# SL869-GL868-Rx.net
KiCad netlist of a schematic drawn in EAGLE
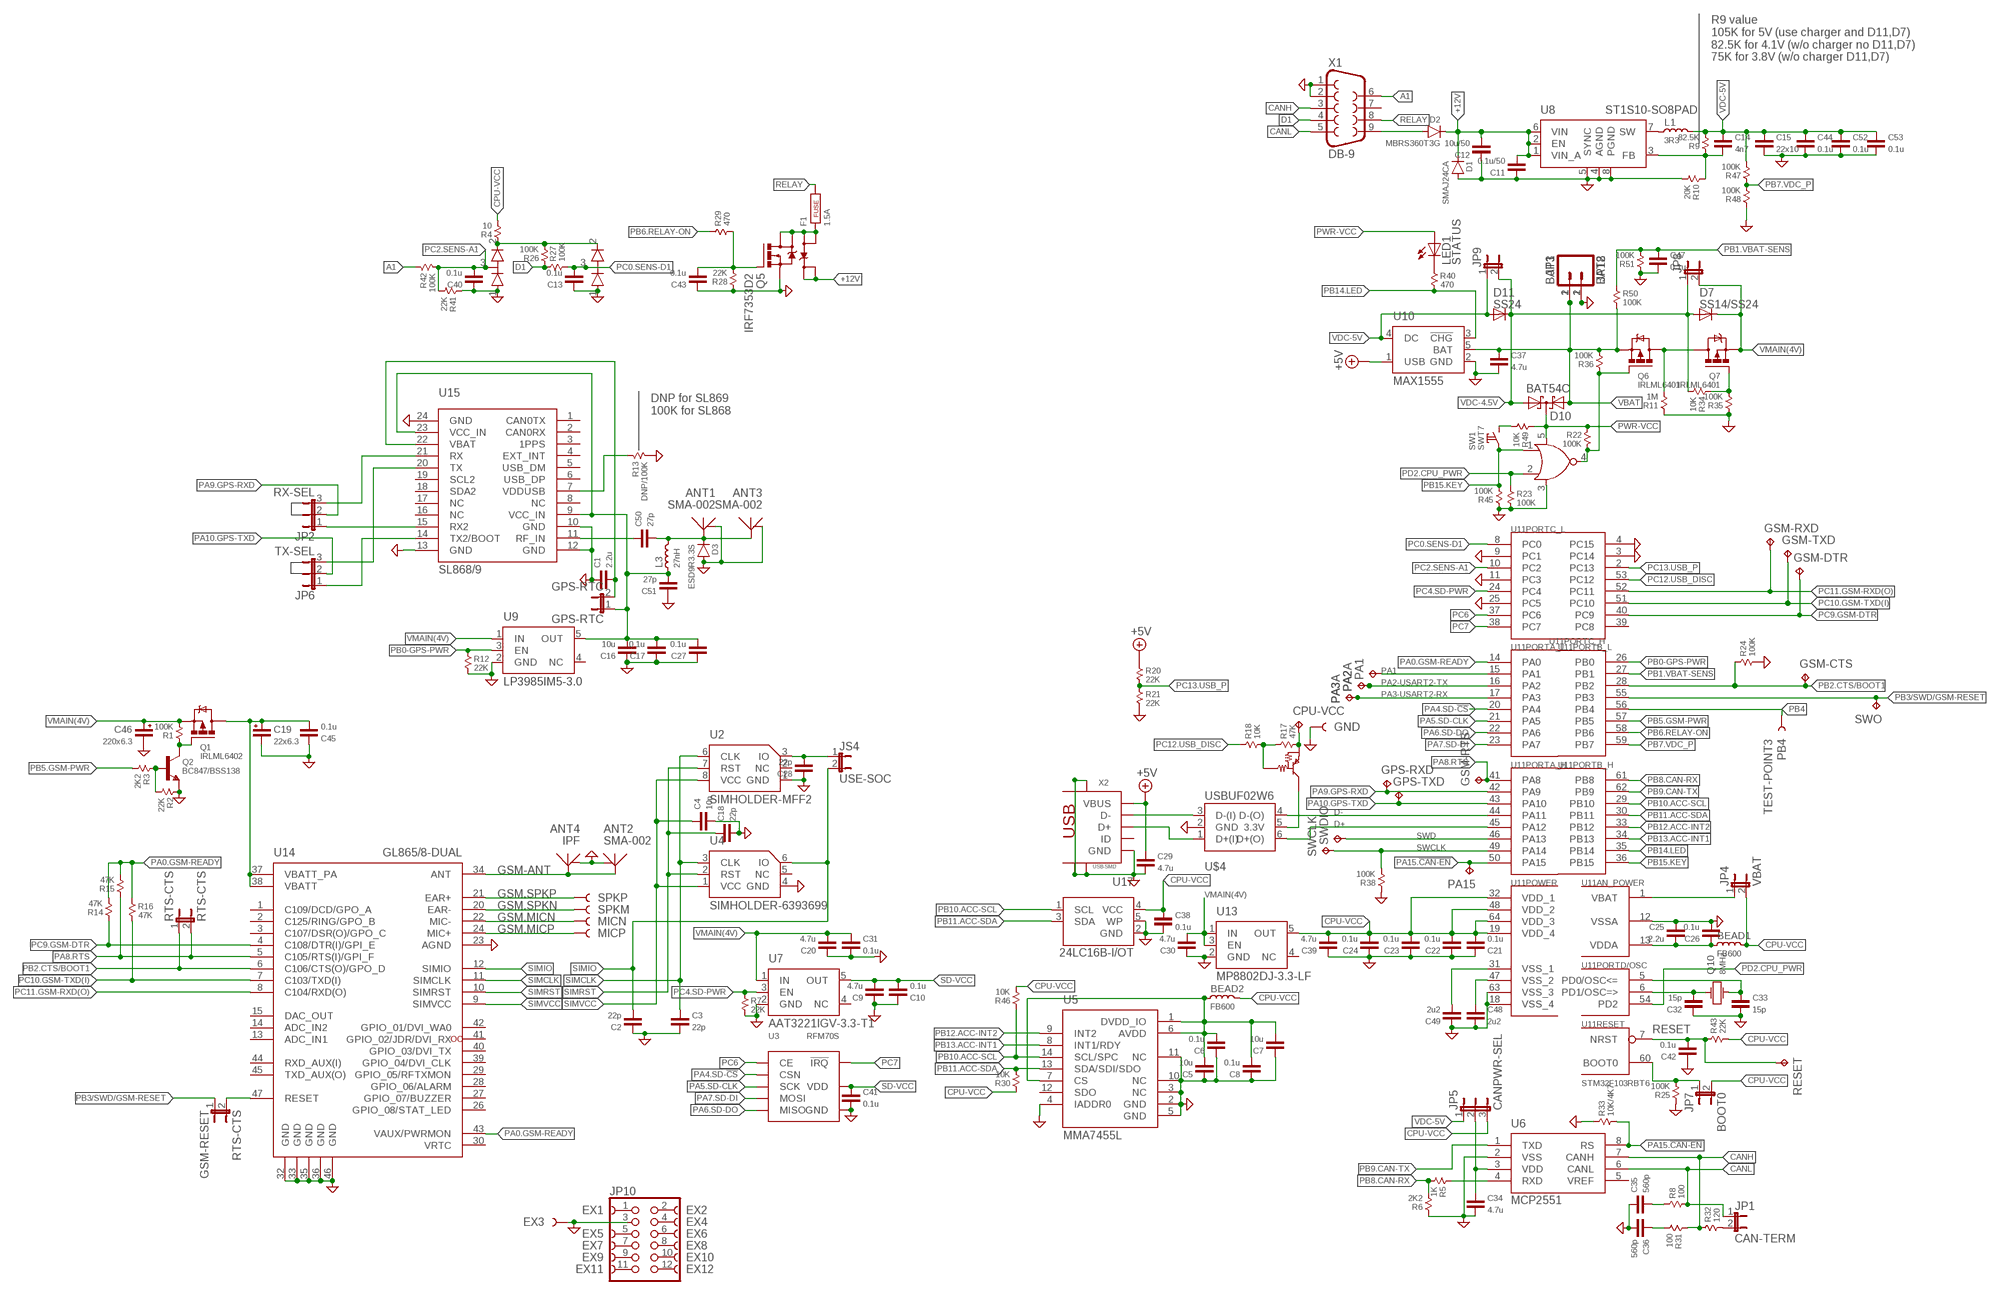
[diagram p0: schematic, sheet 1]

(export (version "E")
  (design (tool "Eeschema 10.0.6"))
  (components
    (comp (ref "ANT1")
      (value "SMA-002")
      (footprint "eagle-import:SMA-002")
      (libsource (lib "eagle-import") (part "ANTENNA-SMA-002"))
    )
    (comp (ref "ANT2")
      (value "SMA-002")
      (footprint "eagle-import:SMA-002")
      (libsource (lib "eagle-import") (part "ANTENNA-SMA-002"))
    )
    (comp (ref "ANT3")
      (value "SMA-002")
      (footprint "eagle-import:MM9329")
      (libsource (lib "eagle-import") (part "ANTENNA-IPF"))
    )
    (comp (ref "ANT4")
      (value "IPF")
      (footprint "eagle-import:MM9329")
      (libsource (lib "eagle-import") (part "ANTENNA-IPF"))
    )
    (comp (ref "BEAD1")
      (value "FB600")
      (footprint "eagle-import:0603")
      (libsource (lib "eagle-import") (part "INDUCTOR-0603"))
    )
    (comp (ref "BEAD2")
      (value "FB600")
      (footprint "eagle-import:0603")
      (libsource (lib "eagle-import") (part "INDUCTOR-0603"))
    )
    (comp (ref "C1")
      (value "2.2u")
      (footprint "eagle-import:0603")
      (libsource (lib "eagle-import") (part "CAP-0603"))
    )
    (comp (ref "C2")
      (value "22p")
      (footprint "eagle-import:0603")
      (libsource (lib "eagle-import") (part "CAP-0603"))
    )
    (comp (ref "C3")
      (value "22p")
      (footprint "eagle-import:0603")
      (libsource (lib "eagle-import") (part "CAP-0603"))
    )
    (comp (ref "C4")
      (value "10n")
      (footprint "eagle-import:0603")
      (libsource (lib "eagle-import") (part "CAP-0603"))
    )
    (comp (ref "C5")
      (value "10u")
      (footprint "eagle-import:0603")
      (libsource (lib "eagle-import") (part "CAP-0603"))
    )
    (comp (ref "C6")
      (value "0.1u")
      (footprint "eagle-import:0603")
      (libsource (lib "eagle-import") (part "CAP-0603"))
    )
    (comp (ref "C7")
      (value "10u")
      (footprint "eagle-import:0603")
      (libsource (lib "eagle-import") (part "CAP-0603"))
    )
    (comp (ref "C8")
      (value "0.1u")
      (footprint "eagle-import:0603")
      (libsource (lib "eagle-import") (part "CAP-0603"))
    )
    (comp (ref "C9")
      (value "4.7u")
      (footprint "eagle-import:0603")
      (libsource (lib "eagle-import") (part "CAP-0603"))
    )
    (comp (ref "C10")
      (value "0.1u")
      (footprint "eagle-import:0603")
      (libsource (lib "eagle-import") (part "CAP-0603"))
    )
    (comp (ref "C11")
      (value "0.1u/50")
      (footprint "eagle-import:0603")
      (libsource (lib "eagle-import") (part "CAP-0603"))
    )
    (comp (ref "C12")
      (value "10u/50")
      (footprint "eagle-import:1206")
      (libsource (lib "eagle-import") (part "CAP-1206"))
    )
    (comp (ref "C13")
      (value "0.1u")
      (footprint "eagle-import:0603")
      (libsource (lib "eagle-import") (part "CAP-0603"))
    )
    (comp (ref "C14")
      (value "4n7")
      (footprint "eagle-import:0603")
      (libsource (lib "eagle-import") (part "CAP-0603"))
    )
    (comp (ref "C15")
      (value "22x10")
      (footprint "eagle-import:1206")
      (libsource (lib "eagle-import") (part "CAP-1206"))
    )
    (comp (ref "C16")
      (value "10u")
      (footprint "eagle-import:0603")
      (libsource (lib "eagle-import") (part "CAP-0603"))
    )
    (comp (ref "C17")
      (value "0.1u")
      (footprint "eagle-import:0603")
      (libsource (lib "eagle-import") (part "CAP-0603"))
    )
    (comp (ref "C18")
      (value "22p")
      (footprint "eagle-import:0603")
      (libsource (lib "eagle-import") (part "CAP-0603"))
    )
    (comp (ref "C19")
      (value "22x6.3")
      (footprint "eagle-import:CT3528")
      (libsource (lib "eagle-import") (part "CAP-POL-3528"))
    )
    (comp (ref "C20")
      (value "4.7u")
      (footprint "eagle-import:0603")
      (libsource (lib "eagle-import") (part "CAP-0603"))
    )
    (comp (ref "C21")
      (value "0.1u")
      (footprint "eagle-import:0603")
      (libsource (lib "eagle-import") (part "CAP-0603"))
    )
    (comp (ref "C22")
      (value "0.1u")
      (footprint "eagle-import:0603")
      (libsource (lib "eagle-import") (part "CAP-0603"))
    )
    (comp (ref "C23")
      (value "0.1u")
      (footprint "eagle-import:0603")
      (libsource (lib "eagle-import") (part "CAP-0603"))
    )
    (comp (ref "C24")
      (value "0.1u")
      (footprint "eagle-import:0603")
      (libsource (lib "eagle-import") (part "CAP-0603"))
    )
    (comp (ref "C25")
      (value "2.2u")
      (footprint "eagle-import:0603")
      (libsource (lib "eagle-import") (part "CAP-0603"))
    )
    (comp (ref "C26")
      (value "0.1u")
      (footprint "eagle-import:0603")
      (libsource (lib "eagle-import") (part "CAP-0603"))
    )
    (comp (ref "C27")
      (value "0.1u")
      (footprint "eagle-import:0603")
      (libsource (lib "eagle-import") (part "CAP-0603"))
    )
    (comp (ref "C28")
      (value "22p")
      (footprint "eagle-import:0603")
      (libsource (lib "eagle-import") (part "CAP-0603"))
    )
    (comp (ref "C29")
      (value "4.7u")
      (footprint "eagle-import:0603")
      (libsource (lib "eagle-import") (part "CAP-0603"))
    )
    (comp (ref "C30")
      (value "4.7u")
      (footprint "eagle-import:0603")
      (libsource (lib "eagle-import") (part "CAP-0603"))
    )
    (comp (ref "C31")
      (value "0.1u")
      (footprint "eagle-import:0603")
      (libsource (lib "eagle-import") (part "CAP-0603"))
    )
    (comp (ref "C32")
      (value "15p")
      (footprint "eagle-import:0603")
      (libsource (lib "eagle-import") (part "CAP-0603"))
    )
    (comp (ref "C33")
      (value "15p")
      (footprint "eagle-import:0603")
      (libsource (lib "eagle-import") (part "CAP-0603"))
    )
    (comp (ref "C34")
      (value "4.7u")
      (footprint "eagle-import:0603")
      (libsource (lib "eagle-import") (part "CAP-0603"))
    )
    (comp (ref "C35")
      (value "560p")
      (footprint "eagle-import:0603")
      (libsource (lib "eagle-import") (part "CAP-0603"))
    )
    (comp (ref "C36")
      (value "560p")
      (footprint "eagle-import:0603")
      (libsource (lib "eagle-import") (part "CAP-0603"))
    )
    (comp (ref "C37")
      (value "4.7u")
      (footprint "eagle-import:0603")
      (libsource (lib "eagle-import") (part "CAP-0603"))
    )
    (comp (ref "C38")
      (value "0.1u")
      (footprint "eagle-import:0603")
      (libsource (lib "eagle-import") (part "CAP-0603"))
    )
    (comp (ref "C39")
      (value "4.7u")
      (footprint "eagle-import:0603")
      (libsource (lib "eagle-import") (part "CAP-0603"))
    )
    (comp (ref "C40")
      (value "0.1u")
      (footprint "eagle-import:0603")
      (libsource (lib "eagle-import") (part "CAP-0603"))
    )
    (comp (ref "C41")
      (value "0.1u")
      (footprint "eagle-import:0603")
      (libsource (lib "eagle-import") (part "CAP-0603"))
    )
    (comp (ref "C42")
      (value "0.1u")
      (footprint "eagle-import:0603")
      (libsource (lib "eagle-import") (part "CAP-0603"))
    )
    (comp (ref "C43")
      (value "0.1u")
      (footprint "eagle-import:0603")
      (libsource (lib "eagle-import") (part "CAP-0603"))
    )
    (comp (ref "C44")
      (value "0.1u")
      (footprint "eagle-import:0603")
      (libsource (lib "eagle-import") (part "CAP-0603"))
    )
    (comp (ref "C45")
      (value "0.1u")
      (footprint "eagle-import:0603")
      (libsource (lib "eagle-import") (part "CAP-0603"))
    )
    (comp (ref "C46")
      (value "220x6.3")
      (footprint "eagle-import:CT7343")
      (libsource (lib "eagle-import") (part "CAP-POL-7343"))
    )
    (comp (ref "C47")
      (value "0.1u")
      (footprint "eagle-import:0603")
      (libsource (lib "eagle-import") (part "CAP-0603"))
    )
    (comp (ref "C48")
      (value "2u2")
      (footprint "eagle-import:0603")
      (libsource (lib "eagle-import") (part "CAP-0603"))
    )
    (comp (ref "C49")
      (value "2u2")
      (footprint "eagle-import:0603")
      (libsource (lib "eagle-import") (part "CAP-0603"))
    )
    (comp (ref "C50")
      (value "27p")
      (footprint "eagle-import:0603")
      (libsource (lib "eagle-import") (part "CAP-0603"))
    )
    (comp (ref "C51")
      (value "27p")
      (footprint "eagle-import:0603")
      (libsource (lib "eagle-import") (part "CAP-0603"))
    )
    (comp (ref "C52")
      (value "0.1u")
      (footprint "eagle-import:0603")
      (libsource (lib "eagle-import") (part "CAP-0603"))
    )
    (comp (ref "C53")
      (value "0.1u")
      (footprint "eagle-import:0603")
      (libsource (lib "eagle-import") (part "CAP-0603"))
    )
    (comp (ref "CPU-VCC")
      (value "TPTP09R")
      (footprint "eagle-import:TP09R")
      (libsource (lib "eagle-import") (part "TPTP09R"))
    )
    (comp (ref "D1")
      (value "SMAJ24CA")
      (footprint "eagle-import:SMA")
      (libsource (lib "eagle-import") (part "DIODE-SMA"))
    )
    (comp (ref "D2")
      (value "MBRS360T3G")
      (footprint "eagle-import:SMC")
      (libsource (lib "eagle-import") (part "DIODE-SMC"))
    )
    (comp (ref "D3")
      (value "ESD9R3.3S")
      (footprint "eagle-import:SOD-923")
      (libsource (lib "eagle-import") (part "DIODE-ESD9"))
    )
    (comp (ref "D4")
      (value "BAV99")
      (footprint "eagle-import:SOT-23")
      (libsource (lib "eagle-import") (part "BAV99"))
    )
    (comp (ref "D7")
      (value "SS14/SS24")
      (footprint "eagle-import:SMA-DIODE")
      (libsource (lib "eagle-import") (part "DIODESMA"))
    )
    (comp (ref "D10")
      (value "BAT54C")
      (footprint "eagle-import:SOT23")
      (libsource (lib "eagle-import") (part "BAT54C"))
    )
    (comp (ref "D11")
      (value "SS24")
      (footprint "eagle-import:SMA-DIODE")
      (libsource (lib "eagle-import") (part "DIODESMA"))
    )
    (comp (ref "D14")
      (value "BAV99")
      (footprint "eagle-import:SOT-23")
      (libsource (lib "eagle-import") (part "BAV99"))
    )
    (comp (ref "EX1")
      (value "TEST-POINT1")
      (footprint "eagle-import:PAD.1X1")
      (libsource (lib "eagle-import") (part "TEST-POINT1"))
    )
    (comp (ref "EX2")
      (value "TEST-POINT1")
      (footprint "eagle-import:PAD.1X1")
      (libsource (lib "eagle-import") (part "TEST-POINT1"))
    )
    (comp (ref "EX3")
      (value "TEST-POINT1")
      (footprint "eagle-import:PAD.1X1")
      (libsource (lib "eagle-import") (part "TEST-POINT1"))
    )
    (comp (ref "EX4")
      (value "TEST-POINT1")
      (footprint "eagle-import:PAD.1X1")
      (libsource (lib "eagle-import") (part "TEST-POINT1"))
    )
    (comp (ref "EX5")
      (value "TEST-POINT1")
      (footprint "eagle-import:PAD.1X1")
      (libsource (lib "eagle-import") (part "TEST-POINT1"))
    )
    (comp (ref "EX6")
      (value "TEST-POINT1")
      (footprint "eagle-import:PAD.1X1")
      (libsource (lib "eagle-import") (part "TEST-POINT1"))
    )
    (comp (ref "EX7")
      (value "TEST-POINT1")
      (footprint "eagle-import:PAD.1X1")
      (libsource (lib "eagle-import") (part "TEST-POINT1"))
    )
    (comp (ref "EX8")
      (value "TEST-POINT1")
      (footprint "eagle-import:PAD.1X1")
      (libsource (lib "eagle-import") (part "TEST-POINT1"))
    )
    (comp (ref "EX9")
      (value "TEST-POINT1")
      (footprint "eagle-import:PAD.1X1")
      (libsource (lib "eagle-import") (part "TEST-POINT1"))
    )
    (comp (ref "EX10")
      (value "TEST-POINT1")
      (footprint "eagle-import:PAD.1X1")
      (libsource (lib "eagle-import") (part "TEST-POINT1"))
    )
    (comp (ref "EX11")
      (value "TEST-POINT1")
      (footprint "eagle-import:PAD.1X1")
      (libsource (lib "eagle-import") (part "TEST-POINT1"))
    )
    (comp (ref "EX12")
      (value "TEST-POINT1")
      (footprint "eagle-import:PAD.1X1")
      (libsource (lib "eagle-import") (part "TEST-POINT1"))
    )
    (comp (ref "F1")
      (value "1.5A")
      (footprint "eagle-import:1812")
      (libsource (lib "eagle-import") (part "FUSE"))
    )
    (comp (ref "GND")
      (value "TEST-POINT3")
      (footprint "eagle-import:PAD.03X.03")
      (libsource (lib "eagle-import") (part "TEST-POINT3"))
    )
    (comp (ref "GPS-RTC")
      (value "GPS-RTC")
      (footprint "eagle-import:SJ_2S-NO")
      (libsource (lib "eagle-import") (part "JUMPER-2SMD-NO"))
    )
    (comp (ref "GPS-RXD")
      (value "TPTP07R")
      (footprint "eagle-import:TP07R")
      (libsource (lib "eagle-import") (part "TPTP07R"))
    )
    (comp (ref "GPS-TXD")
      (value "TPTP07R")
      (footprint "eagle-import:TP07R")
      (libsource (lib "eagle-import") (part "TPTP07R"))
    )
    (comp (ref "GSM-CTS")
      (value "TPTP07R")
      (footprint "eagle-import:TP07R")
      (libsource (lib "eagle-import") (part "TPTP07R"))
    )
    (comp (ref "GSM-DTR")
      (value "TPTP07R")
      (footprint "eagle-import:TP07R")
      (libsource (lib "eagle-import") (part "TPTP07R"))
    )
    (comp (ref "GSM-RESET")
      (value "RTS-CTS")
      (footprint "eagle-import:SJ_2S-NO")
      (libsource (lib "eagle-import") (part "JUMPER-2SMD-NO"))
    )
    (comp (ref "GSM-RTS")
      (value "TPTP07R")
      (footprint "eagle-import:TP07R")
      (libsource (lib "eagle-import") (part "TPTP07R"))
    )
    (comp (ref "GSM-RXD")
      (value "TPTP07R")
      (footprint "eagle-import:TP07R")
      (libsource (lib "eagle-import") (part "TPTP07R"))
    )
    (comp (ref "GSM-TXD")
      (value "TPTP07R")
      (footprint "eagle-import:TP07R")
      (libsource (lib "eagle-import") (part "TPTP07R"))
    )
    (comp (ref "JP1")
      (value "CAN-TERM")
      (footprint "eagle-import:SJ_2S-NO")
      (libsource (lib "eagle-import") (part "JUMPER-2SMD-NO"))
    )
    (comp (ref "JP2")
      (value "RX-SEL")
      (footprint "eagle-import:SJ_3")
      (libsource (lib "eagle-import") (part "JUMPER-3SMD"))
    )
    (comp (ref "JP3")
      (value "BAT2")
      (footprint "eagle-import:S2B-PH")
      (libsource (lib "eagle-import") (part "M02-JST-2MM-SMT"))
    )
    (comp (ref "JP4")
      (value "VBAT")
      (footprint "eagle-import:SJ_2S-NO")
      (libsource (lib "eagle-import") (part "JUMPER-2SMD-NO"))
    )
    (comp (ref "JP5")
      (value "CANPWR-SEL")
      (footprint "eagle-import:SJ_3")
      (libsource (lib "eagle-import") (part "JUMPER-3SMD"))
    )
    (comp (ref "JP6")
      (value "TX-SEL")
      (footprint "eagle-import:SJ_3")
      (libsource (lib "eagle-import") (part "JUMPER-3SMD"))
    )
    (comp (ref "JP7")
      (value "BOOT0")
      (footprint "eagle-import:SJ_2S-NO")
      (libsource (lib "eagle-import") (part "JUMPER-2SMD-NO"))
    )
    (comp (ref "JP8")
      (value "JUMPER-2SMD-NO")
      (footprint "eagle-import:SJ_2S-NO")
      (libsource (lib "eagle-import") (part "JUMPER-2SMD-NO"))
    )
    (comp (ref "JP9")
      (value "JUMPER-2SMD-NO")
      (footprint "eagle-import:SJ_2S-NO")
      (libsource (lib "eagle-import") (part "JUMPER-2SMD-NO"))
    )
    (comp (ref "JP10")
      (value "PINHD-2X6")
      (footprint "eagle-import:2X06")
      (libsource (lib "eagle-import") (part "PINHD-2X6"))
    )
    (comp (ref "JP18")
      (value "BAT1")
      (footprint "eagle-import:CI1102M1H")
      (libsource (lib "eagle-import") (part "M02-CI1102M1H"))
    )
    (comp (ref "JS4")
      (value "USE-SOC")
      (footprint "eagle-import:SJ_2S-NO")
      (libsource (lib "eagle-import") (part "JUMPER-2SMD-NO"))
    )
    (comp (ref "L1")
      (value "3R3")
      (footprint "eagle-import:CDRH6D38NP")
      (libsource (lib "eagle-import") (part "INDUCTOR-CDRH6D38NP"))
    )
    (comp (ref "L3")
      (value "27nH")
      (footprint "eagle-import:0603")
      (libsource (lib "eagle-import") (part "INDUCTOR-0603"))
    )
    (comp (ref "LED1")
      (value "STATUS")
      (footprint "eagle-import:LED3MM")
      (libsource (lib "eagle-import") (part "LED3MM"))
    )
    (comp (ref "MICN")
      (value "TEST-POINT1")
      (footprint "eagle-import:PAD.1X1")
      (libsource (lib "eagle-import") (part "TEST-POINT1"))
    )
    (comp (ref "MICP")
      (value "TEST-POINT1")
      (footprint "eagle-import:PAD.1X1")
      (libsource (lib "eagle-import") (part "TEST-POINT1"))
    )
    (comp (ref "PA1")
      (value "TPTP08R")
      (footprint "eagle-import:TP08R")
      (libsource (lib "eagle-import") (part "TPTP08R"))
    )
    (comp (ref "PA2")
      (value "TPTP08R")
      (footprint "eagle-import:TP08R")
      (libsource (lib "eagle-import") (part "TPTP08R"))
    )
    (comp (ref "PA2A")
      (value "TPTP07R")
      (footprint "eagle-import:TP07R")
      (libsource (lib "eagle-import") (part "TPTP07R"))
    )
    (comp (ref "PA3")
      (value "TPTP08R")
      (footprint "eagle-import:TP08R")
      (libsource (lib "eagle-import") (part "TPTP08R"))
    )
    (comp (ref "PA3A")
      (value "TPTP07R")
      (footprint "eagle-import:TP07R")
      (libsource (lib "eagle-import") (part "TPTP07R"))
    )
    (comp (ref "PA15")
      (value "TPTP07R")
      (footprint "eagle-import:TP07R")
      (libsource (lib "eagle-import") (part "TPTP07R"))
    )
    (comp (ref "PB4")
      (value "TEST-POINT3")
      (footprint "eagle-import:PAD.03X.03")
      (libsource (lib "eagle-import") (part "TEST-POINT3"))
    )
    (comp (ref "Q1")
      (value "IRLML6402")
      (footprint "eagle-import:SOT-23")
      (libsource (lib "eagle-import") (part "IRLML6402"))
    )
    (comp (ref "Q2")
      (value "BC847/BSS138")
      (footprint "eagle-import:SOT-23")
      (libsource (lib "eagle-import") (part "NPNBC847"))
    )
    (comp (ref "Q5")
      (value "IRF7353D2")
      (footprint "eagle-import:SO08")
      (libsource (lib "eagle-import") (part "IRF7353D2"))
    )
    (comp (ref "Q6")
      (value "IRLML6401")
      (footprint "eagle-import:SOT-23")
      (libsource (lib "eagle-import") (part "IRLML6401"))
    )
    (comp (ref "Q7")
      (value "IRLML6401")
      (footprint "eagle-import:SOT-23")
      (libsource (lib "eagle-import") (part "IRLML6401"))
    )
    (comp (ref "Q10")
      (value "8MHz")
      (footprint "eagle-import:KX-9A")
      (libsource (lib "eagle-import") (part "CRYSTAL-KX-9A"))
    )
    (comp (ref "R1")
      (value "100K")
      (footprint "eagle-import:0603")
      (libsource (lib "eagle-import") (part "RESISTOR-0603"))
    )
    (comp (ref "R2")
      (value "22K")
      (footprint "eagle-import:0603")
      (libsource (lib "eagle-import") (part "RESISTOR-0603"))
    )
    (comp (ref "R3")
      (value "2K2")
      (footprint "eagle-import:0603")
      (libsource (lib "eagle-import") (part "RESISTOR-0603"))
    )
    (comp (ref "R4")
      (value "10")
      (footprint "eagle-import:0603")
      (libsource (lib "eagle-import") (part "RESISTOR-0603"))
    )
    (comp (ref "R5")
      (value "1K")
      (footprint "eagle-import:0603")
      (libsource (lib "eagle-import") (part "RESISTOR-0603"))
    )
    (comp (ref "R6")
      (value "2K2")
      (footprint "eagle-import:0603")
      (libsource (lib "eagle-import") (part "RESISTOR-0603"))
    )
    (comp (ref "R7")
      (value "22K")
      (footprint "eagle-import:0603")
      (libsource (lib "eagle-import") (part "RESISTOR-0603"))
    )
    (comp (ref "R8")
      (value "100")
      (footprint "eagle-import:0603")
      (libsource (lib "eagle-import") (part "RESISTOR-0603"))
    )
    (comp (ref "R9")
      (value "82.5K")
      (footprint "eagle-import:0603")
      (libsource (lib "eagle-import") (part "RESISTOR-0603"))
    )
    (comp (ref "R10")
      (value "20K")
      (footprint "eagle-import:0603")
      (libsource (lib "eagle-import") (part "RESISTOR-0603"))
    )
    (comp (ref "R11")
      (value "1M")
      (footprint "eagle-import:0603")
      (libsource (lib "eagle-import") (part "RESISTOR-0603"))
    )
    (comp (ref "R12")
      (value "22K")
      (footprint "eagle-import:0603")
      (libsource (lib "eagle-import") (part "RESISTOR-0603"))
    )
    (comp (ref "R13")
      (value "DNP/100K")
      (footprint "eagle-import:0603")
      (libsource (lib "eagle-import") (part "RESISTOR-0603"))
    )
    (comp (ref "R14")
      (value "47K")
      (footprint "eagle-import:0603")
      (libsource (lib "eagle-import") (part "RESISTOR-0603"))
    )
    (comp (ref "R15")
      (value "47K")
      (footprint "eagle-import:0603")
      (libsource (lib "eagle-import") (part "RESISTOR-0603"))
    )
    (comp (ref "R16")
      (value "47K")
      (footprint "eagle-import:0603")
      (libsource (lib "eagle-import") (part "RESISTOR-0603"))
    )
    (comp (ref "R17")
      (value "47K")
      (footprint "eagle-import:0603")
      (libsource (lib "eagle-import") (part "RESISTOR-0603"))
    )
    (comp (ref "R18")
      (value "10K")
      (footprint "eagle-import:0603")
      (libsource (lib "eagle-import") (part "RESISTOR-0603"))
    )
    (comp (ref "R20")
      (value "22K")
      (footprint "eagle-import:0603")
      (libsource (lib "eagle-import") (part "RESISTOR-0603"))
    )
    (comp (ref "R21")
      (value "22K")
      (footprint "eagle-import:0603")
      (libsource (lib "eagle-import") (part "RESISTOR-0603"))
    )
    (comp (ref "R22")
      (value "100K")
      (footprint "eagle-import:0603")
      (libsource (lib "eagle-import") (part "RESISTOR-0603"))
    )
    (comp (ref "R23")
      (value "100K")
      (footprint "eagle-import:0603")
      (libsource (lib "eagle-import") (part "RESISTOR-0603"))
    )
    (comp (ref "R24")
      (value "100K")
      (footprint "eagle-import:0603")
      (libsource (lib "eagle-import") (part "RESISTOR-0603"))
    )
    (comp (ref "R25")
      (value "100K")
      (footprint "eagle-import:0603")
      (libsource (lib "eagle-import") (part "RESISTOR-0603"))
    )
    (comp (ref "R26")
      (value "100K")
      (footprint "eagle-import:0603")
      (libsource (lib "eagle-import") (part "RESISTOR-0603"))
    )
    (comp (ref "R27")
      (value "100K")
      (footprint "eagle-import:0603")
      (libsource (lib "eagle-import") (part "RESISTOR-0603"))
    )
    (comp (ref "R28")
      (value "22K")
      (footprint "eagle-import:0603")
      (libsource (lib "eagle-import") (part "RESISTOR-0603"))
    )
    (comp (ref "R29")
      (value "470")
      (footprint "eagle-import:0603")
      (libsource (lib "eagle-import") (part "RESISTOR-0603"))
    )
    (comp (ref "R30")
      (value "10K")
      (footprint "eagle-import:0603")
      (libsource (lib "eagle-import") (part "RESISTOR-0603"))
    )
    (comp (ref "R31")
      (value "100")
      (footprint "eagle-import:0603")
      (libsource (lib "eagle-import") (part "RESISTOR-0603"))
    )
    (comp (ref "R32")
      (value "120")
      (footprint "eagle-import:0603")
      (libsource (lib "eagle-import") (part "RESISTOR-0603"))
    )
    (comp (ref "R33")
      (value "10K/4K7")
      (footprint "eagle-import:0603")
      (libsource (lib "eagle-import") (part "RESISTOR-0603"))
    )
    (comp (ref "R34")
      (value "10K")
      (footprint "eagle-import:0603")
      (libsource (lib "eagle-import") (part "RESISTOR-0603"))
    )
    (comp (ref "R35")
      (value "100K")
      (footprint "eagle-import:0603")
      (libsource (lib "eagle-import") (part "RESISTOR-0603"))
    )
    (comp (ref "R36")
      (value "100K")
      (footprint "eagle-import:0603")
      (libsource (lib "eagle-import") (part "RESISTOR-0603"))
    )
    (comp (ref "R38")
      (value "100K")
      (footprint "eagle-import:0603")
      (libsource (lib "eagle-import") (part "RESISTOR-0603"))
    )
    (comp (ref "R40")
      (value "470")
      (footprint "eagle-import:0603")
      (libsource (lib "eagle-import") (part "RESISTOR-0603"))
    )
    (comp (ref "R41")
      (value "22K")
      (footprint "eagle-import:0603")
      (libsource (lib "eagle-import") (part "RESISTOR-0603"))
    )
    (comp (ref "R42")
      (value "100K")
      (footprint "eagle-import:0603")
      (libsource (lib "eagle-import") (part "RESISTOR-0603"))
    )
    (comp (ref "R43")
      (value "22K")
      (footprint "eagle-import:0603")
      (libsource (lib "eagle-import") (part "RESISTOR-0603"))
    )
    (comp (ref "R45")
      (value "100K")
      (footprint "eagle-import:0603")
      (libsource (lib "eagle-import") (part "RESISTOR-0603"))
    )
    (comp (ref "R46")
      (value "10K")
      (footprint "eagle-import:0603")
      (libsource (lib "eagle-import") (part "RESISTOR-0603"))
    )
    (comp (ref "R47")
      (value "100K")
      (footprint "eagle-import:0603")
      (libsource (lib "eagle-import") (part "RESISTOR-0603"))
    )
    (comp (ref "R48")
      (value "100K")
      (footprint "eagle-import:0603")
      (libsource (lib "eagle-import") (part "RESISTOR-0603"))
    )
    (comp (ref "R49")
      (value "10K")
      (footprint "eagle-import:0603")
      (libsource (lib "eagle-import") (part "RESISTOR-0603"))
    )
    (comp (ref "R50")
      (value "100K")
      (footprint "eagle-import:0603")
      (libsource (lib "eagle-import") (part "RESISTOR-0603"))
    )
    (comp (ref "R51")
      (value "100K")
      (footprint "eagle-import:0603")
      (libsource (lib "eagle-import") (part "RESISTOR-0603"))
    )
    (comp (ref "RESET")
      (value "TPTP09R")
      (footprint "eagle-import:TP09R")
      (libsource (lib "eagle-import") (part "TPTP09R"))
    )
    (comp (ref "RTS-CTS")
      (value "RTS-CTS")
      (footprint "eagle-import:SJ_2S-NO")
      (libsource (lib "eagle-import") (part "JUMPER-2SMD-NO"))
    )
    (comp (ref "SPKM")
      (value "TEST-POINT1")
      (footprint "eagle-import:PAD.1X1")
      (libsource (lib "eagle-import") (part "TEST-POINT1"))
    )
    (comp (ref "SPKP")
      (value "TEST-POINT1")
      (footprint "eagle-import:PAD.1X1")
      (libsource (lib "eagle-import") (part "TEST-POINT1"))
    )
    (comp (ref "SW1")
      (value "SWT7")
      (footprint "eagle-import:SWT-7")
      (libsource (lib "eagle-import") (part "SWITCH-2-SWT7"))
    )
    (comp (ref "SWCLK")
      (value "TPTP09R")
      (footprint "eagle-import:TP09R")
      (libsource (lib "eagle-import") (part "TPTP09R"))
    )
    (comp (ref "SWDIO")
      (value "TPTP09R")
      (footprint "eagle-import:TP09R")
      (libsource (lib "eagle-import") (part "TPTP09R"))
    )
    (comp (ref "SWO")
      (value "TPTP07R")
      (footprint "eagle-import:TP07R")
      (libsource (lib "eagle-import") (part "TPTP07R"))
    )
    (comp (ref "U$3")
      (value "PDTA114ET")
      (footprint "eagle-import:SOT-23")
      (libsource (lib "eagle-import") (part "PDTA114ET"))
    )
    (comp (ref "U$4")
      (value "USBUF02W6")
      (footprint "eagle-import:SOT323-6")
      (libsource (lib "eagle-import") (part "USBUF02W6"))
    )
    (comp (ref "U1")
      (value "74LVC1G02GV")
      (footprint "eagle-import:SOT-753")
      (libsource (lib "eagle-import") (part "74LVC1G02GV"))
    )
    (comp (ref "U2")
      (value "SIMHOLDER-MFF2")
      (footprint "eagle-import:MFF2")
      (libsource (lib "eagle-import") (part "SIMHOLDER-MFF2"))
    )
    (comp (ref "U3")
      (value "RFM70S")
      (footprint "eagle-import:RFM70S")
      (libsource (lib "eagle-import") (part "RFM70S"))
    )
    (comp (ref "U4")
      (value "SIMHOLDER-6393699")
      (footprint "eagle-import:6393699-1")
      (libsource (lib "eagle-import") (part "SIMHOLDER-6393699"))
    )
    (comp (ref "U5")
      (value "MMA7455L")
      (footprint "eagle-import:LGA14")
      (libsource (lib "eagle-import") (part "MMA7455L"))
    )
    (comp (ref "U6")
      (value "MCP2551")
      (footprint "eagle-import:SO08")
      (libsource (lib "eagle-import") (part "MCP2551"))
    )
    (comp (ref "U7")
      (value "AAT3221IGV-3.3-T1")
      (footprint "eagle-import:SOT23-5")
      (libsource (lib "eagle-import") (part "TPS73033"))
    )
    (comp (ref "U8")
      (value "ST1S10-SO8PAD")
      (footprint "eagle-import:SO08-EPAD")
      (libsource (lib "eagle-import") (part "ST1S10-SO8PAD"))
    )
    (comp (ref "U9")
      (value "LP3985IM5-3.0")
      (footprint "eagle-import:SOT23-5")
      (libsource (lib "eagle-import") (part "TPS73033"))
    )
    (comp (ref "U10")
      (value "MAX1555")
      (footprint "eagle-import:SOT23-5")
      (libsource (lib "eagle-import") (part "MAX1555"))
    )
    (comp (ref "U11")
      (value "STM32F103RBT6")
      (footprint "eagle-import:TQFP64")
      (libsource (lib "eagle-import") (part "STM32F10XRXT6"))
    )
    (comp (ref "U13")
      (value "MP8802DJ-3.3-LF")
      (footprint "eagle-import:SOT23-5")
      (libsource (lib "eagle-import") (part "TPS73033"))
    )
    (comp (ref "U14")
      (value "GL865/8-DUAL")
      (footprint "eagle-import:GL865_8-DUAL")
      (libsource (lib "eagle-import") (part "GL865/8-DUAL"))
    )
    (comp (ref "U15")
      (value "SL868/9")
      (footprint "eagle-import:SL868_9")
      (libsource (lib "eagle-import") (part "SL868/9"))
    )
    (comp (ref "U17")
      (value "24LC16B-I/OT")
      (footprint "eagle-import:SOT23-5")
      (libsource (lib "eagle-import") (part "24LC01B-SOT23"))
    )
    (comp (ref "X1")
      (value "DB-9")
      (footprint "eagle-import:DB9")
      (libsource (lib "eagle-import") (part "DB9"))
    )
    (comp (ref "X2")
      (value "USB-SMD")
      (footprint "eagle-import:USB-MINIB")
      (libsource (lib "eagle-import") (part "USB-SMD"))
    )
  )
  (nets
    (net (code "1") (name "+5V") (class "Default")
      (node (ref "C29") (pin "2") (pinfunction "2_2") (pintype "passive"))
      (node (ref "R20") (pin "1") (pinfunction "1_1") (pintype "passive"))
      (node (ref "U10") (pin "1") (pinfunction "USB_1") (pintype "input"))
      (node (ref "X2") (pin "VBUS") (pinfunction "VBUS_VBUS") (pintype "passive"))
    )
    (net (code "2") (name "+12V") (class "Default")
      (node (ref "C11") (pin "1") (pinfunction "1_1") (pintype "passive"))
      (node (ref "C12") (pin "1") (pinfunction "1_1") (pintype "passive"))
      (node (ref "D1") (pin "P$1") (pinfunction "C_P$1") (pintype "passive"))
      (node (ref "D2") (pin "P$1") (pinfunction "C_P$1") (pintype "passive"))
      (node (ref "Q5") (pin "7") (pinfunction "K_7") (pintype "passive"))
      (node (ref "Q5") (pin "8") (pinfunction "K_8") (pintype "passive"))
      (node (ref "U8") (pin "1") (pinfunction "VIN_A_1") (pintype "passive"))
      (node (ref "U8") (pin "2") (pinfunction "EN_2") (pintype "passive"))
      (node (ref "U8") (pin "6") (pinfunction "VIN_6") (pintype "passive"))
    )
    (net (code "3") (name "/D+") (class "Default")
      (node (ref "U$4") (pin "6") (pinfunction "D+(O)_6") (pintype "passive"))
      (node (ref "U11") (pin "45") (pinfunction "PA12_45") (pintype "bidirectional"))
    )
    (net (code "4") (name "/D-") (class "Default")
      (node (ref "U$4") (pin "4") (pinfunction "D-(O)_4") (pintype "passive"))
      (node (ref "U11") (pin "44") (pinfunction "PA11_44") (pintype "bidirectional"))
    )
    (net (code "5") (name "/GSM-ANT") (class "Default")
      (node (ref "ANT2") (pin "A") (pinfunction "ANT_A") (pintype "passive"))
      (node (ref "ANT4") (pin "1") (pinfunction "ANT_1") (pintype "passive"))
      (node (ref "U14") (pin "34") (pinfunction "ANT_34") (pintype "passive"))
    )
    (net (code "6") (name "/GSM.MICN") (class "Default")
      (node (ref "MICN") (pin "P$1") (pinfunction "1_P$1") (pintype "bidirectional"))
      (node (ref "U14") (pin "22") (pinfunction "MIC-_22") (pintype "passive"))
    )
    (net (code "7") (name "/GSM.MICP") (class "Default")
      (node (ref "MICP") (pin "P$1") (pinfunction "1_P$1") (pintype "bidirectional"))
      (node (ref "U14") (pin "24") (pinfunction "MIC+_24") (pintype "passive"))
    )
    (net (code "8") (name "/GSM.SPKN") (class "Default")
      (node (ref "SPKM") (pin "P$1") (pinfunction "1_P$1") (pintype "bidirectional"))
      (node (ref "U14") (pin "20") (pinfunction "EAR-_20") (pintype "passive"))
    )
    (net (code "9") (name "/GSM.SPKP") (class "Default")
      (node (ref "SPKP") (pin "P$1") (pinfunction "1_P$1") (pintype "bidirectional"))
      (node (ref "U14") (pin "21") (pinfunction "EAR+_21") (pintype "passive"))
    )
    (net (code "10") (name "/PA1") (class "Default")
      (node (ref "PA1") (pin "TP") (pinfunction "TP_TP") (pintype "input"))
      (node (ref "U11") (pin "15") (pinfunction "PA1_15") (pintype "bidirectional"))
    )
    (net (code "11") (name "/PA2-USART2-TX") (class "Default")
      (node (ref "PA2") (pin "TP") (pinfunction "TP_TP") (pintype "input"))
      (node (ref "PA2A") (pin "TP") (pinfunction "TP_TP") (pintype "input"))
      (node (ref "U11") (pin "16") (pinfunction "PA2_16") (pintype "bidirectional"))
    )
    (net (code "12") (name "/PA3-USART2-RX") (class "Default")
      (node (ref "PA3") (pin "TP") (pinfunction "TP_TP") (pintype "input"))
      (node (ref "PA3A") (pin "TP") (pinfunction "TP_TP") (pintype "input"))
      (node (ref "U11") (pin "17") (pinfunction "PA3_17") (pintype "bidirectional"))
    )
    (net (code "13") (name "/PA4.SD-~{CS}") (class "Default")
      (node (ref "U11") (pin "20") (pinfunction "PA4_20") (pintype "bidirectional"))
      (node (ref "U3") (pin "CSN") (pinfunction "CSN_CSN") (pintype "input"))
    )
    (net (code "14") (name "/PA15.~{CAN-EN}") (class "Default")
      (node (ref "PA15") (pin "TP") (pinfunction "TP_TP") (pintype "input"))
      (node (ref "R33") (pin "2") (pinfunction "2_2") (pintype "passive"))
      (node (ref "U11") (pin "50") (pinfunction "PA15_50") (pintype "bidirectional"))
      (node (ref "U6") (pin "8") (pinfunction "RS_8") (pintype "bidirectional"))
    )
    (net (code "15") (name "/RESET") (class "Default")
      (node (ref "C42") (pin "1") (pinfunction "1_1") (pintype "passive"))
      (node (ref "R43") (pin "1") (pinfunction "1_1") (pintype "passive"))
      (node (ref "RESET") (pin "TP") (pinfunction "TP_TP") (pintype "input"))
      (node (ref "U11") (pin "7") (pinfunction "NRST_7") (pintype "input"))
    )
    (net (code "16") (name "/SWCLK") (class "Default")
      (node (ref "R38") (pin "2") (pinfunction "2_2") (pintype "passive"))
      (node (ref "SWCLK") (pin "TP") (pinfunction "TP_TP") (pintype "input"))
      (node (ref "U11") (pin "49") (pinfunction "PA14_49") (pintype "bidirectional"))
    )
    (net (code "17") (name "/SWD") (class "Default")
      (node (ref "SWDIO") (pin "TP") (pinfunction "TP_TP") (pintype "input"))
      (node (ref "U11") (pin "46") (pinfunction "PA13_46") (pintype "bidirectional"))
    )
    (net (code "18") (name "A1") (class "Default")
      (node (ref "R42") (pin "1") (pinfunction "1_1") (pintype "passive"))
      (node (ref "X1") (pin "6") (pinfunction "6_6") (pintype "passive"))
    )
    (net (code "19") (name "CANH") (class "Default")
      (node (ref "R31") (pin "1") (pinfunction "1_1") (pintype "passive"))
      (node (ref "R32") (pin "1") (pinfunction "1_1") (pintype "passive"))
      (node (ref "U6") (pin "7") (pinfunction "CANH_7") (pintype "bidirectional"))
      (node (ref "X1") (pin "3") (pinfunction "3_3") (pintype "passive"))
    )
    (net (code "20") (name "CANL") (class "Default")
      (node (ref "JP1") (pin "1") (pinfunction "1_1") (pintype "passive"))
      (node (ref "R8") (pin "2") (pinfunction "2_2") (pintype "passive"))
      (node (ref "U6") (pin "6") (pinfunction "CANL_6") (pintype "bidirectional"))
      (node (ref "X1") (pin "5") (pinfunction "5_5") (pintype "passive"))
    )
    (net (code "21") (name "CPU-VCC") (class "Default")
      (node (ref "BEAD1") (pin "2") (pinfunction "2_2") (pintype "passive"))
      (node (ref "BEAD2") (pin "2") (pinfunction "2_2") (pintype "passive"))
      (node (ref "C21") (pin "1") (pinfunction "1_1") (pintype "passive"))
      (node (ref "C22") (pin "1") (pinfunction "1_1") (pintype "passive"))
      (node (ref "C23") (pin "1") (pinfunction "1_1") (pintype "passive"))
      (node (ref "C24") (pin "1") (pinfunction "1_1") (pintype "passive"))
      (node (ref "C38") (pin "2") (pinfunction "2_2") (pintype "passive"))
      (node (ref "C39") (pin "1") (pinfunction "1_1") (pintype "passive"))
      (node (ref "CPU-VCC") (pin "TP") (pinfunction "TP_TP") (pintype "input"))
      (node (ref "JP4") (pin "2") (pinfunction "2_2") (pintype "passive"))
      (node (ref "JP5") (pin "3") (pinfunction "3_3") (pintype "passive"))
      (node (ref "JP7") (pin "2") (pinfunction "2_2") (pintype "passive"))
      (node (ref "R17") (pin "2") (pinfunction "2_2") (pintype "passive"))
      (node (ref "R30") (pin "1") (pinfunction "1_1") (pintype "passive"))
      (node (ref "R4") (pin "2") (pinfunction "2_2") (pintype "passive"))
      (node (ref "R43") (pin "2") (pinfunction "2_2") (pintype "passive"))
      (node (ref "R46") (pin "2") (pinfunction "2_2") (pintype "passive"))
      (node (ref "U$3") (pin "2") (pinfunction "2_2") (pintype "passive"))
      (node (ref "U11") (pin "19") (pinfunction "VDD_4_19") (pintype "power_in"))
      (node (ref "U11") (pin "32") (pinfunction "VDD_1_32") (pintype "power_in"))
      (node (ref "U11") (pin "48") (pinfunction "VDD_2_48") (pintype "power_in"))
      (node (ref "U11") (pin "64") (pinfunction "VDD_3_64") (pintype "power_in"))
      (node (ref "U13") (pin "5") (pinfunction "OUT_5") (pintype "passive"))
      (node (ref "U17") (pin "4") (pinfunction "VCC_4") (pintype "power_in"))
    )
    (net (code "22") (name "D1") (class "Default")
      (node (ref "R26") (pin "1") (pinfunction "1_1") (pintype "passive"))
      (node (ref "R27") (pin "1") (pinfunction "1_1") (pintype "passive"))
      (node (ref "X1") (pin "4") (pinfunction "4_4") (pintype "passive"))
    )
    (net (code "23") (name "GND") (class "Default")
      (node (ref "ANT1") (pin "GND@1") (pinfunction "GND_GND@1") (pintype "power_in"))
      (node (ref "ANT2") (pin "GND@1") (pinfunction "GND_GND@1") (pintype "power_in"))
      (node (ref "ANT3") (pin "2") (pinfunction "GND_2") (pintype "power_in"))
      (node (ref "ANT4") (pin "2") (pinfunction "GND_2") (pintype "power_in"))
      (node (ref "C1") (pin "2") (pinfunction "2_2") (pintype "passive"))
      (node (ref "C10") (pin "2") (pinfunction "2_2") (pintype "passive"))
      (node (ref "C11") (pin "2") (pinfunction "2_2") (pintype "passive"))
      (node (ref "C12") (pin "2") (pinfunction "2_2") (pintype "passive"))
      (node (ref "C13") (pin "2") (pinfunction "2_2") (pintype "passive"))
      (node (ref "C15") (pin "1") (pinfunction "1_1") (pintype "passive"))
      (node (ref "C16") (pin "2") (pinfunction "2_2") (pintype "passive"))
      (node (ref "C17") (pin "2") (pinfunction "2_2") (pintype "passive"))
      (node (ref "C18") (pin "1") (pinfunction "1_1") (pintype "passive"))
      (node (ref "C19") (pin "-") (pinfunction "-_-") (pintype "passive"))
      (node (ref "C2") (pin "2") (pinfunction "2_2") (pintype "passive"))
      (node (ref "C20") (pin "2") (pinfunction "2_2") (pintype "passive"))
      (node (ref "C21") (pin "2") (pinfunction "2_2") (pintype "passive"))
      (node (ref "C22") (pin "2") (pinfunction "2_2") (pintype "passive"))
      (node (ref "C23") (pin "2") (pinfunction "2_2") (pintype "passive"))
      (node (ref "C24") (pin "2") (pinfunction "2_2") (pintype "passive"))
      (node (ref "C25") (pin "2") (pinfunction "2_2") (pintype "passive"))
      (node (ref "C26") (pin "1") (pinfunction "1_1") (pintype "passive"))
      (node (ref "C27") (pin "2") (pinfunction "2_2") (pintype "passive"))
      (node (ref "C28") (pin "2") (pinfunction "2_2") (pintype "passive"))
      (node (ref "C29") (pin "1") (pinfunction "1_1") (pintype "passive"))
      (node (ref "C3") (pin "1") (pinfunction "1_1") (pintype "passive"))
      (node (ref "C30") (pin "2") (pinfunction "2_2") (pintype "passive"))
      (node (ref "C31") (pin "1") (pinfunction "1_1") (pintype "passive"))
      (node (ref "C32") (pin "2") (pinfunction "2_2") (pintype "passive"))
      (node (ref "C33") (pin "1") (pinfunction "1_1") (pintype "passive"))
      (node (ref "C34") (pin "1") (pinfunction "1_1") (pintype "passive"))
      (node (ref "C35") (pin "2") (pinfunction "2_2") (pintype "passive"))
      (node (ref "C36") (pin "1") (pinfunction "1_1") (pintype "passive"))
      (node (ref "C37") (pin "1") (pinfunction "1_1") (pintype "passive"))
      (node (ref "C38") (pin "1") (pinfunction "1_1") (pintype "passive"))
      (node (ref "C39") (pin "2") (pinfunction "2_2") (pintype "passive"))
      (node (ref "C4") (pin "1") (pinfunction "1_1") (pintype "passive"))
      (node (ref "C40") (pin "2") (pinfunction "2_2") (pintype "passive"))
      (node (ref "C41") (pin "1") (pinfunction "1_1") (pintype "passive"))
      (node (ref "C42") (pin "2") (pinfunction "2_2") (pintype "passive"))
      (node (ref "C43") (pin "2") (pinfunction "2_2") (pintype "passive"))
      (node (ref "C44") (pin "1") (pinfunction "1_1") (pintype "passive"))
      (node (ref "C45") (pin "2") (pinfunction "2_2") (pintype "passive"))
      (node (ref "C46") (pin "-") (pinfunction "-_-") (pintype "passive"))
      (node (ref "C47") (pin "1") (pinfunction "1_1") (pintype "passive"))
      (node (ref "C48") (pin "1") (pinfunction "1_1") (pintype "passive"))
      (node (ref "C49") (pin "2") (pinfunction "2_2") (pintype "passive"))
      (node (ref "C5") (pin "2") (pinfunction "2_2") (pintype "passive"))
      (node (ref "C51") (pin "2") (pinfunction "2_2") (pintype "passive"))
      (node (ref "C52") (pin "1") (pinfunction "1_1") (pintype "passive"))
      (node (ref "C53") (pin "1") (pinfunction "1_1") (pintype "passive"))
      (node (ref "C6") (pin "2") (pinfunction "2_2") (pintype "passive"))
      (node (ref "C7") (pin "2") (pinfunction "2_2") (pintype "passive"))
      (node (ref "C8") (pin "2") (pinfunction "2_2") (pintype "passive"))
      (node (ref "C9") (pin "2") (pinfunction "2_2") (pintype "passive"))
      (node (ref "D1") (pin "P$2") (pinfunction "A_P$2") (pintype "passive"))
      (node (ref "D14") (pin "1") (pinfunction "-_1") (pintype "passive"))
      (node (ref "D3") (pin "2") (pinfunction "A_2") (pintype "passive"))
      (node (ref "D4") (pin "1") (pinfunction "-_1") (pintype "passive"))
      (node (ref "EX3") (pin "P$1") (pinfunction "1_P$1") (pintype "bidirectional"))
      (node (ref "GND") (pin "P$1") (pinfunction "1_P$1") (pintype "bidirectional"))
      (node (ref "JP10") (pin "3") (pinfunction "3_3") (pintype "passive"))
      (node (ref "JP18") (pin "2") (pinfunction "2_2") (pintype "passive"))
      (node (ref "JP3") (pin "1") (pinfunction "1_1") (pintype "passive"))
      (node (ref "Q2") (pin "2") (pinfunction "E_2") (pintype "passive"))
      (node (ref "Q5") (pin "3") (pinfunction "S_3") (pintype "passive"))
      (node (ref "R10") (pin "2") (pinfunction "2_2") (pintype "passive"))
      (node (ref "R11") (pin "1") (pinfunction "1_1") (pintype "passive"))
      (node (ref "R12") (pin "2") (pinfunction "2_2") (pintype "passive"))
      (node (ref "R13") (pin "2") (pinfunction "2_2") (pintype "passive"))
      (node (ref "R2") (pin "1") (pinfunction "1_1") (pintype "passive"))
      (node (ref "R21") (pin "2") (pinfunction "2_2") (pintype "passive"))
      (node (ref "R23") (pin "2") (pinfunction "2_2") (pintype "passive"))
      (node (ref "R24") (pin "2") (pinfunction "2_2") (pintype "passive"))
      (node (ref "R25") (pin "1") (pinfunction "1_1") (pintype "passive"))
      (node (ref "R28") (pin "1") (pinfunction "1_1") (pintype "passive"))
      (node (ref "R33") (pin "1") (pinfunction "1_1") (pintype "passive"))
      (node (ref "R35") (pin "1") (pinfunction "1_1") (pintype "passive"))
      (node (ref "R38") (pin "1") (pinfunction "1_1") (pintype "passive"))
      (node (ref "R41") (pin "1") (pinfunction "1_1") (pintype "passive"))
      (node (ref "R45") (pin "1") (pinfunction "1_1") (pintype "passive"))
      (node (ref "R48") (pin "1") (pinfunction "1_1") (pintype "passive"))
      (node (ref "R51") (pin "1") (pinfunction "1_1") (pintype "passive"))
      (node (ref "R6") (pin "1") (pinfunction "1_1") (pintype "passive"))
      (node (ref "R7") (pin "2") (pinfunction "2_2") (pintype "passive"))
      (node (ref "U$4") (pin "2") (pinfunction "GND_2") (pintype "passive"))
      (node (ref "U1") (pin "3") (pinfunction "GND_3") (pintype "power_in"))
      (node (ref "U10") (pin "2") (pinfunction "GND_2") (pintype "power_in"))
      (node (ref "U11") (pin "11") (pinfunction "PC3_11") (pintype "bidirectional"))
      (node (ref "U11") (pin "12") (pinfunction "VSSA_12") (pintype "power_in"))
      (node (ref "U11") (pin "18") (pinfunction "VSS_4_18") (pintype "power_in"))
      (node (ref "U11") (pin "25") (pinfunction "PC5_25") (pintype "bidirectional"))
      (node (ref "U11") (pin "3") (pinfunction "PC14_3") (pintype "bidirectional"))
      (node (ref "U11") (pin "4") (pinfunction "PC15_4") (pintype "bidirectional"))
      (node (ref "U11") (pin "63") (pinfunction "VSS_3_63") (pintype "power_in"))
      (node (ref "U11") (pin "9") (pinfunction "PC1_9") (pintype "bidirectional"))
      (node (ref "U13") (pin "2") (pinfunction "GND_2") (pintype "power_in"))
      (node (ref "U14") (pin "23") (pinfunction "AGND_23") (pintype "passive"))
      (node (ref "U14") (pin "32") (pinfunction "GND_32") (pintype "power_in"))
      (node (ref "U14") (pin "33") (pinfunction "GND_33") (pintype "power_in"))
      (node (ref "U14") (pin "35") (pinfunction "GND_35") (pintype "power_in"))
      (node (ref "U14") (pin "36") (pinfunction "GND_36") (pintype "power_in"))
      (node (ref "U14") (pin "46") (pinfunction "GND_46") (pintype "power_in"))
      (node (ref "U15") (pin "10") (pinfunction "GND_10") (pintype "power_in"))
      (node (ref "U15") (pin "12") (pinfunction "GND_12") (pintype "power_in"))
      (node (ref "U15") (pin "13") (pinfunction "GND_13") (pintype "power_in"))
      (node (ref "U15") (pin "24") (pinfunction "GND_24") (pintype "power_in"))
      (node (ref "U17") (pin "2") (pinfunction "GND_2") (pintype "power_in"))
      (node (ref "U17") (pin "5") (pinfunction "WP_5") (pintype "input"))
      (node (ref "U2") (pin "1") (pinfunction "GND_1") (pintype "power_in"))
      (node (ref "U3") (pin "GND") (pinfunction "GND_GND") (pintype "power_in"))
      (node (ref "U4") (pin "4") (pinfunction "GND_4") (pintype "power_in"))
      (node (ref "U5") (pin "10") (pinfunction "NC_10") (pintype "passive"))
      (node (ref "U5") (pin "11") (pinfunction "NC_11") (pintype "passive"))
      (node (ref "U5") (pin "2") (pinfunction "GND_2") (pintype "power_in"))
      (node (ref "U5") (pin "3") (pinfunction "NC_3") (pintype "passive"))
      (node (ref "U5") (pin "4") (pinfunction "IADDR0_4") (pintype "input"))
      (node (ref "U5") (pin "5") (pinfunction "GND_5") (pintype "power_in"))
      (node (ref "U6") (pin "2") (pinfunction "VSS_2") (pintype "bidirectional"))
      (node (ref "U7") (pin "2") (pinfunction "GND_2") (pintype "power_in"))
      (node (ref "U8") (pin "4") (pinfunction "AGND_4") (pintype "passive"))
      (node (ref "U8") (pin "5") (pinfunction "SYNC_5") (pintype "passive"))
      (node (ref "U8") (pin "8") (pinfunction "PGND_8") (pintype "power_in"))
      (node (ref "U9") (pin "2") (pinfunction "GND_2") (pintype "power_in"))
      (node (ref "X1") (pin "1") (pinfunction "1_1") (pintype "passive"))
      (node (ref "X1") (pin "2") (pinfunction "2_2") (pintype "passive"))
      (node (ref "X2") (pin "GND") (pinfunction "GND_GND") (pintype "power_in"))
      (node (ref "X2") (pin "GND@1") (pinfunction "GND_GND@1") (pintype "power_in"))
      (node (ref "X2") (pin "GND@2") (pinfunction "GND_GND@2") (pintype "power_in"))
      (node (ref "X2") (pin "GND@3") (pinfunction "GND_GND@3") (pintype "power_in"))
      (node (ref "X2") (pin "GND@4") (pinfunction "GND_GND@4") (pintype "power_in"))
    )
    (net (code "24") (name "Net-(ANT1-ANT)") (class "Default")
      (node (ref "ANT1") (pin "A") (pinfunction "ANT_A") (pintype "passive"))
      (node (ref "ANT3") (pin "1") (pinfunction "ANT_1") (pintype "passive"))
      (node (ref "C50") (pin "1") (pinfunction "1_1") (pintype "passive"))
      (node (ref "D3") (pin "1") (pinfunction "C_1") (pintype "passive"))
      (node (ref "L3") (pin "2") (pinfunction "2_2") (pintype "passive"))
    )
    (net (code "25") (name "Net-(C35-Pad1)") (class "Default")
      (node (ref "C35") (pin "1") (pinfunction "1_1") (pintype "passive"))
      (node (ref "R8") (pin "1") (pinfunction "1_1") (pintype "passive"))
    )
    (net (code "26") (name "Net-(C36-Pad2)") (class "Default")
      (node (ref "C36") (pin "2") (pinfunction "2_2") (pintype "passive"))
      (node (ref "R31") (pin "2") (pinfunction "2_2") (pintype "passive"))
    )
    (net (code "27") (name "Net-(D2-A)") (class "Default")
      (node (ref "D2") (pin "P$2") (pinfunction "A_P$2") (pintype "passive"))
      (node (ref "X1") (pin "9") (pinfunction "9_9") (pintype "passive"))
    )
    (net (code "28") (name "Net-(D14-+)") (class "Default")
      (node (ref "D14") (pin "2") (pinfunction "+_2") (pintype "passive"))
      (node (ref "D4") (pin "2") (pinfunction "+_2") (pintype "passive"))
      (node (ref "R26") (pin "2") (pinfunction "2_2") (pintype "passive"))
      (node (ref "R4") (pin "1") (pinfunction "1_1") (pintype "passive"))
    )
    (net (code "29") (name "Net-(EX1-1)") (class "Default")
      (node (ref "EX1") (pin "P$1") (pinfunction "1_P$1") (pintype "bidirectional"))
      (node (ref "JP10") (pin "1") (pinfunction "1_1") (pintype "passive"))
    )
    (net (code "30") (name "Net-(EX2-1)") (class "Default")
      (node (ref "EX2") (pin "P$1") (pinfunction "1_P$1") (pintype "bidirectional"))
      (node (ref "JP10") (pin "2") (pinfunction "2_2") (pintype "passive"))
    )
    (net (code "31") (name "Net-(EX4-1)") (class "Default")
      (node (ref "EX4") (pin "P$1") (pinfunction "1_P$1") (pintype "bidirectional"))
      (node (ref "JP10") (pin "4") (pinfunction "4_4") (pintype "passive"))
    )
    (net (code "32") (name "Net-(EX5-1)") (class "Default")
      (node (ref "EX5") (pin "P$1") (pinfunction "1_P$1") (pintype "bidirectional"))
      (node (ref "JP10") (pin "5") (pinfunction "5_5") (pintype "passive"))
    )
    (net (code "33") (name "Net-(EX6-1)") (class "Default")
      (node (ref "EX6") (pin "P$1") (pinfunction "1_P$1") (pintype "bidirectional"))
      (node (ref "JP10") (pin "6") (pinfunction "6_6") (pintype "passive"))
    )
    (net (code "34") (name "Net-(EX7-1)") (class "Default")
      (node (ref "EX7") (pin "P$1") (pinfunction "1_P$1") (pintype "bidirectional"))
      (node (ref "JP10") (pin "7") (pinfunction "7_7") (pintype "passive"))
    )
    (net (code "35") (name "Net-(EX8-1)") (class "Default")
      (node (ref "EX8") (pin "P$1") (pinfunction "1_P$1") (pintype "bidirectional"))
      (node (ref "JP10") (pin "8") (pinfunction "8_8") (pintype "passive"))
    )
    (net (code "36") (name "Net-(EX9-1)") (class "Default")
      (node (ref "EX9") (pin "P$1") (pinfunction "1_P$1") (pintype "bidirectional"))
      (node (ref "JP10") (pin "9") (pinfunction "9_9") (pintype "passive"))
    )
    (net (code "37") (name "Net-(EX10-1)") (class "Default")
      (node (ref "EX10") (pin "P$1") (pinfunction "1_P$1") (pintype "bidirectional"))
      (node (ref "JP10") (pin "10") (pinfunction "10_10") (pintype "passive"))
    )
    (net (code "38") (name "Net-(EX11-1)") (class "Default")
      (node (ref "EX11") (pin "P$1") (pinfunction "1_P$1") (pintype "bidirectional"))
      (node (ref "JP10") (pin "11") (pinfunction "11_11") (pintype "passive"))
    )
    (net (code "39") (name "Net-(EX12-1)") (class "Default")
      (node (ref "EX12") (pin "P$1") (pinfunction "1_P$1") (pintype "bidirectional"))
      (node (ref "JP10") (pin "12") (pinfunction "12_12") (pintype "passive"))
    )
    (net (code "40") (name "Net-(F1-Pad1)") (class "Default")
      (node (ref "F1") (pin "1") (pinfunction "1_1") (pintype "passive"))
      (node (ref "Q5") (pin "1") (pinfunction "A_1") (pintype "passive"))
      (node (ref "Q5") (pin "2") (pinfunction "A_2") (pintype "passive"))
      (node (ref "Q5") (pin "5") (pinfunction "D_5") (pintype "passive"))
      (node (ref "Q5") (pin "6") (pinfunction "D_6") (pintype "passive"))
    )
    (net (code "41") (name "Net-(JP1-Pad2)") (class "Default")
      (node (ref "JP1") (pin "2") (pinfunction "2_2") (pintype "passive"))
      (node (ref "R32") (pin "2") (pinfunction "2_2") (pintype "passive"))
    )
    (net (code "42") (name "Net-(L1-1)") (class "Default")
      (node (ref "L1") (pin "P$1") (pinfunction "1_P$1") (pintype "passive"))
      (node (ref "U8") (pin "7") (pinfunction "SW_7") (pintype "passive"))
    )
    (net (code "43") (name "Net-(LED1-C)") (class "Default")
      (node (ref "LED1") (pin "K") (pinfunction "C_K") (pintype "passive"))
      (node (ref "R40") (pin "1") (pinfunction "1_1") (pintype "passive"))
    )
    (net (code "44") (name "Net-(Q1-D)") (class "Default")
      (node (ref "C19") (pin "+") (pinfunction "+_+") (pintype "passive"))
      (node (ref "C45") (pin "1") (pinfunction "1_1") (pintype "passive"))
      (node (ref "Q1") (pin "3") (pinfunction "D_3") (pintype "passive"))
      (node (ref "U14") (pin "37") (pinfunction "VBATT_PA_37") (pintype "passive"))
      (node (ref "U14") (pin "38") (pinfunction "VBATT_38") (pintype "passive"))
    )
    (net (code "45") (name "Net-(Q1-G)") (class "Default")
      (node (ref "Q1") (pin "1") (pinfunction "G_1") (pintype "passive"))
      (node (ref "Q2") (pin "3") (pinfunction "C_3") (pintype "passive"))
      (node (ref "R1") (pin "1") (pinfunction "1_1") (pintype "passive"))
    )
    (net (code "46") (name "Net-(Q2-B)") (class "Default")
      (node (ref "Q2") (pin "1") (pinfunction "B_1") (pintype "passive"))
      (node (ref "R2") (pin "2") (pinfunction "2_2") (pintype "passive"))
      (node (ref "R3") (pin "1") (pinfunction "1_1") (pintype "passive"))
    )
    (net (code "47") (name "Net-(Q5-G)") (class "Default")
      (node (ref "C43") (pin "1") (pinfunction "1_1") (pintype "passive"))
      (node (ref "Q5") (pin "4") (pinfunction "G_4") (pintype "passive"))
      (node (ref "R28") (pin "2") (pinfunction "2_2") (pintype "passive"))
      (node (ref "R29") (pin "2") (pinfunction "2_2") (pintype "passive"))
    )
    (net (code "48") (name "Net-(Q6-D)") (class "Default")
      (node (ref "Q6") (pin "3") (pinfunction "D_3") (pintype "passive"))
      (node (ref "Q7") (pin "3") (pinfunction "D_3") (pintype "passive"))
      (node (ref "R11") (pin "2") (pinfunction "2_2") (pintype "passive"))
    )
    (net (code "49") (name "Net-(Q6-G)") (class "Default")
      (node (ref "Q6") (pin "1") (pinfunction "G_1") (pintype "passive"))
      (node (ref "R22") (pin "2") (pinfunction "2_2") (pintype "passive"))
      (node (ref "R36") (pin "1") (pinfunction "1_1") (pintype "passive"))
      (node (ref "U1") (pin "4") (pinfunction "Y_4") (pintype "output"))
    )
    (net (code "50") (name "Net-(Q7-G)") (class "Default")
      (node (ref "Q7") (pin "1") (pinfunction "G_1") (pintype "passive"))
      (node (ref "R34") (pin "1") (pinfunction "1_1") (pintype "passive"))
      (node (ref "R35") (pin "2") (pinfunction "2_2") (pintype "passive"))
    )
    (net (code "51") (name "Net-(Q10-2)") (class "Default")
      (node (ref "C33") (pin "2") (pinfunction "2_2") (pintype "passive"))
      (node (ref "Q10") (pin "3") (pinfunction "2_3") (pintype "passive"))
      (node (ref "U11") (pin "5") (pinfunction "PD0/OSC<=_5") (pintype "bidirectional"))
    )
    (net (code "52") (name "Net-(R17-Pad1)") (class "Default")
      (node (ref "R17") (pin "1") (pinfunction "1_1") (pintype "passive"))
      (node (ref "R18") (pin "2") (pinfunction "2_2") (pintype "passive"))
      (node (ref "U$3") (pin "1") (pinfunction "1_1") (pintype "passive"))
    )
    (net (code "53") (name "Net-(R49-Pad2)") (class "Default")
      (node (ref "R49") (pin "2") (pinfunction "2_2") (pintype "passive"))
      (node (ref "SW1") (pin "2") (pinfunction "2_2") (pintype "passive"))
    )
    (net (code "54") (name "Net-(U$4-3.3V)") (class "Default")
      (node (ref "U$3") (pin "3") (pinfunction "3_3") (pintype "passive"))
      (node (ref "U$4") (pin "5") (pinfunction "3.3V_5") (pintype "passive"))
    )
    (net (code "55") (name "Net-(U$4-D+(I))") (class "Default")
      (node (ref "U$4") (pin "1") (pinfunction "D+(I)_1") (pintype "passive"))
      (node (ref "X2") (pin "D+") (pinfunction "D+_D+") (pintype "bidirectional"))
    )
    (net (code "56") (name "Net-(U$4-D-(I))") (class "Default")
      (node (ref "U$4") (pin "3") (pinfunction "D-(I)_3") (pintype "passive"))
      (node (ref "X2") (pin "D-") (pinfunction "D-_D-") (pintype "bidirectional"))
    )
    (net (code "57") (name "Net-(U2-IO)") (class "Default")
      (node (ref "C28") (pin "1") (pinfunction "1_1") (pintype "passive"))
      (node (ref "JS4") (pin "1") (pinfunction "1_1") (pintype "passive"))
      (node (ref "U2") (pin "3") (pinfunction "IO_3") (pintype "bidirectional"))
    )
    (net (code "58") (name "Net-(U5-AVDD)") (class "Default")
      (node (ref "BEAD2") (pin "1") (pinfunction "1_1") (pintype "passive"))
      (node (ref "C5") (pin "1") (pinfunction "1_1") (pintype "passive"))
      (node (ref "C6") (pin "1") (pinfunction "1_1") (pintype "passive"))
      (node (ref "C7") (pin "1") (pinfunction "1_1") (pintype "passive"))
      (node (ref "C8") (pin "1") (pinfunction "1_1") (pintype "passive"))
      (node (ref "U5") (pin "1") (pinfunction "DVDD_IO_1") (pintype "power_in"))
      (node (ref "U5") (pin "6") (pinfunction "AVDD_6") (pintype "power_in"))
      (node (ref "U5") (pin "7") (pinfunction "CS_7") (pintype "input"))
    )
    (net (code "59") (name "Net-(U6-RXD)") (class "Default")
      (node (ref "R5") (pin "1") (pinfunction "1_1") (pintype "passive"))
      (node (ref "U6") (pin "4") (pinfunction "RXD_4") (pintype "bidirectional"))
    )
    (net (code "60") (name "Net-(U6-VDD)") (class "Default")
      (node (ref "C34") (pin "2") (pinfunction "2_2") (pintype "passive"))
      (node (ref "JP5") (pin "2") (pinfunction "2_2") (pintype "passive"))
      (node (ref "U6") (pin "3") (pinfunction "VDD_3") (pintype "bidirectional"))
    )
    (net (code "61") (name "Net-(U8-FB)") (class "Default")
      (node (ref "C14") (pin "1") (pinfunction "1_1") (pintype "passive"))
      (node (ref "R10") (pin "1") (pinfunction "1_1") (pintype "passive"))
      (node (ref "R9") (pin "1") (pinfunction "1_1") (pintype "passive"))
      (node (ref "U8") (pin "3") (pinfunction "FB_3") (pintype "passive"))
    )
    (net (code "62") (name "Net-(U9-OUT)") (class "Default")
      (node (ref "C16") (pin "1") (pinfunction "1_1") (pintype "passive"))
      (node (ref "C17") (pin "1") (pinfunction "1_1") (pintype "passive"))
      (node (ref "C27") (pin "1") (pinfunction "1_1") (pintype "passive"))
      (node (ref "C51") (pin "1") (pinfunction "1_1") (pintype "passive"))
      (node (ref "GPS-RTC") (pin "1") (pinfunction "1_1") (pintype "passive"))
      (node (ref "L3") (pin "1") (pinfunction "1_1") (pintype "passive"))
      (node (ref "U15") (pin "23") (pinfunction "VCC_IN_23") (pintype "passive"))
      (node (ref "U15") (pin "9") (pinfunction "VCC_IN_9") (pintype "passive"))
      (node (ref "U9") (pin "5") (pinfunction "OUT_5") (pintype "passive"))
    )
    (net (code "63") (name "Net-(U11A-VBAT)") (class "Default")
      (node (ref "JP4") (pin "1") (pinfunction "1_1") (pintype "passive"))
      (node (ref "U11") (pin "1") (pinfunction "VBAT_1") (pintype "power_in"))
    )
    (net (code "64") (name "Net-(U11A-VDDA)") (class "Default")
      (node (ref "BEAD1") (pin "1") (pinfunction "1_1") (pintype "passive"))
      (node (ref "C25") (pin "1") (pinfunction "1_1") (pintype "passive"))
      (node (ref "C26") (pin "2") (pinfunction "2_2") (pintype "passive"))
      (node (ref "U11") (pin "13") (pinfunction "VDDA_13") (pintype "power_in"))
    )
    (net (code "65") (name "Net-(U11H-PD1{slash}OSC=>)") (class "Default")
      (node (ref "C32") (pin "1") (pinfunction "1_1") (pintype "passive"))
      (node (ref "Q10") (pin "1") (pinfunction "1_1") (pintype "passive"))
      (node (ref "U11") (pin "6") (pinfunction "PD1/OSC=>_6") (pintype "bidirectional"))
    )
    (net (code "66") (name "Net-(U11I-VSS_1)") (class "Default")
      (node (ref "C49") (pin "1") (pinfunction "1_1") (pintype "passive"))
      (node (ref "U11") (pin "31") (pinfunction "VSS_1_31") (pintype "power_in"))
    )
    (net (code "67") (name "Net-(U11I-VSS_2)") (class "Default")
      (node (ref "C48") (pin "2") (pinfunction "2_2") (pintype "passive"))
      (node (ref "U11") (pin "47") (pinfunction "VSS_2_47") (pintype "power_in"))
    )
    (net (code "68") (name "Net-(U11J-BOOT0)") (class "Default")
      (node (ref "JP7") (pin "1") (pinfunction "1_1") (pintype "passive"))
      (node (ref "R25") (pin "2") (pinfunction "2_2") (pintype "passive"))
      (node (ref "U11") (pin "60") (pinfunction "BOOT0_60") (pintype "input"))
    )
    (net (code "69") (name "Net-(U14-RESET)") (class "Default")
      (node (ref "GSM-RESET") (pin "2") (pinfunction "2_2") (pintype "passive"))
      (node (ref "U14") (pin "47") (pinfunction "RESET_47") (pintype "input"))
    )
    (net (code "70") (name "Net-(U15-RF_IN)") (class "Default")
      (node (ref "C50") (pin "2") (pinfunction "2_2") (pintype "passive"))
      (node (ref "U15") (pin "11") (pinfunction "RF_IN_11") (pintype "passive"))
    )
    (net (code "71") (name "Net-(U15-RX)") (class "Default")
      (node (ref "JP2") (pin "3") (pinfunction "3_3") (pintype "passive"))
      (node (ref "U15") (pin "21") (pinfunction "RX_21") (pintype "input"))
    )
    (net (code "72") (name "Net-(U15-RX2)") (class "Default")
      (node (ref "JP2") (pin "1") (pinfunction "1_1") (pintype "passive"))
      (node (ref "U15") (pin "15") (pinfunction "RX2_15") (pintype "input"))
    )
    (net (code "73") (name "Net-(U15-TX)") (class "Default")
      (node (ref "JP6") (pin "3") (pinfunction "3_3") (pintype "passive"))
      (node (ref "U15") (pin "20") (pinfunction "TX_20") (pintype "output"))
    )
    (net (code "74") (name "Net-(U15-TX2{slash}BOOT)") (class "Default")
      (node (ref "JP6") (pin "1") (pinfunction "1_1") (pintype "passive"))
      (node (ref "U15") (pin "14") (pinfunction "TX2/BOOT_14") (pintype "output"))
    )
    (net (code "75") (name "Net-(U15-VBAT)") (class "Default")
      (node (ref "C1") (pin "1") (pinfunction "1_1") (pintype "passive"))
      (node (ref "GPS-RTC") (pin "2") (pinfunction "2_2") (pintype "passive"))
      (node (ref "U15") (pin "22") (pinfunction "VBAT_22") (pintype "passive"))
    )
    (net (code "76") (name "Net-(U15-VDDUSB)") (class "Default")
      (node (ref "R13") (pin "1") (pinfunction "1_1") (pintype "passive"))
      (node (ref "U15") (pin "7") (pinfunction "VDDUSB_7") (pintype "bidirectional"))
    )
    (net (code "77") (name "PA0.GSM-READY") (class "Default")
      (node (ref "R14") (pin "2") (pinfunction "2_2") (pintype "passive"))
      (node (ref "R15") (pin "2") (pinfunction "2_2") (pintype "passive"))
      (node (ref "R16") (pin "1") (pinfunction "1_1") (pintype "passive"))
      (node (ref "U11") (pin "14") (pinfunction "PA0_14") (pintype "bidirectional"))
      (node (ref "U14") (pin "43") (pinfunction "VAUX/PWRMON_43") (pintype "output"))
    )
    (net (code "78") (name "PA5.SD-CLK") (class "Default")
      (node (ref "U11") (pin "21") (pinfunction "PA5_21") (pintype "bidirectional"))
      (node (ref "U3") (pin "SCK") (pinfunction "SCK_SCK") (pintype "input"))
    )
    (net (code "79") (name "PA6.SD-DO") (class "Default")
      (node (ref "U11") (pin "22") (pinfunction "PA6_22") (pintype "bidirectional"))
      (node (ref "U3") (pin "MISO") (pinfunction "MISO_MISO") (pintype "tri_state"))
    )
    (net (code "80") (name "PA7.SD-DI") (class "Default")
      (node (ref "U11") (pin "23") (pinfunction "PA7_23") (pintype "bidirectional"))
      (node (ref "U3") (pin "MOSI") (pinfunction "MOSI_MOSI") (pintype "input"))
    )
    (net (code "81") (name "PA8.RTS") (class "Default")
      (node (ref "GSM-RTS") (pin "TP") (pinfunction "TP_TP") (pintype "input"))
      (node (ref "R15") (pin "1") (pinfunction "1_1") (pintype "passive"))
      (node (ref "RTS-CTS") (pin "2") (pinfunction "2_2") (pintype "passive"))
      (node (ref "U11") (pin "41") (pinfunction "PA8_41") (pintype "bidirectional"))
      (node (ref "U14") (pin "5") (pinfunction "C105/RTS(I)/GPI_F_5") (pintype "input"))
    )
    (net (code "82") (name "PA9.GPS-RXD") (class "Default")
      (node (ref "GPS-RXD") (pin "TP") (pinfunction "TP_TP") (pintype "input"))
      (node (ref "JP2") (pin "2") (pinfunction "2_2") (pintype "passive"))
      (node (ref "U11") (pin "42") (pinfunction "PA9_42") (pintype "bidirectional"))
    )
    (net (code "83") (name "PA10.GPS-TXD") (class "Default")
      (node (ref "GPS-TXD") (pin "TP") (pinfunction "TP_TP") (pintype "input"))
      (node (ref "JP6") (pin "2") (pinfunction "2_2") (pintype "passive"))
      (node (ref "U11") (pin "43") (pinfunction "PA10_43") (pintype "bidirectional"))
    )
    (net (code "84") (name "PB0-GPS-PWR") (class "Default")
      (node (ref "R12") (pin "1") (pinfunction "1_1") (pintype "passive"))
      (node (ref "U11") (pin "26") (pinfunction "PB0_26") (pintype "bidirectional"))
      (node (ref "U9") (pin "3") (pinfunction "EN_3") (pintype "input"))
    )
    (net (code "85") (name "PB1.VBAT-SENS") (class "Default")
      (node (ref "C47") (pin "2") (pinfunction "2_2") (pintype "passive"))
      (node (ref "R50") (pin "1") (pinfunction "1_1") (pintype "passive"))
      (node (ref "R51") (pin "2") (pinfunction "2_2") (pintype "passive"))
      (node (ref "U11") (pin "27") (pinfunction "PB1_27") (pintype "bidirectional"))
    )
    (net (code "86") (name "PB2.CTS{slash}BOOT1") (class "Default")
      (node (ref "GSM-CTS") (pin "TP") (pinfunction "TP_TP") (pintype "input"))
      (node (ref "R24") (pin "1") (pinfunction "1_1") (pintype "passive"))
      (node (ref "RTS-CTS") (pin "1") (pinfunction "1_1") (pintype "passive"))
      (node (ref "U11") (pin "28") (pinfunction "PB2_28") (pintype "bidirectional"))
      (node (ref "U14") (pin "6") (pinfunction "C106/CTS(O)/GPO_D_6") (pintype "output"))
    )
    (net (code "87") (name "PB3{slash}SWD{slash}GSM-RESET") (class "Default")
      (node (ref "GSM-RESET") (pin "1") (pinfunction "1_1") (pintype "passive"))
      (node (ref "SWO") (pin "TP") (pinfunction "TP_TP") (pintype "input"))
      (node (ref "U11") (pin "55") (pinfunction "PB3_55") (pintype "bidirectional"))
    )
    (net (code "88") (name "PB4") (class "Default")
      (node (ref "PB4") (pin "P$1") (pinfunction "1_P$1") (pintype "bidirectional"))
      (node (ref "U11") (pin "56") (pinfunction "PB4_56") (pintype "bidirectional"))
    )
    (net (code "89") (name "PB5.GSM-PWR") (class "Default")
      (node (ref "R3") (pin "2") (pinfunction "2_2") (pintype "passive"))
      (node (ref "U11") (pin "57") (pinfunction "PB5_57") (pintype "bidirectional"))
    )
    (net (code "90") (name "PB6.RELAY-ON") (class "Default")
      (node (ref "R29") (pin "1") (pinfunction "1_1") (pintype "passive"))
      (node (ref "U11") (pin "58") (pinfunction "PB6_58") (pintype "bidirectional"))
    )
    (net (code "91") (name "PB7.VDC_P") (class "Default")
      (node (ref "R47") (pin "1") (pinfunction "1_1") (pintype "passive"))
      (node (ref "R48") (pin "2") (pinfunction "2_2") (pintype "passive"))
      (node (ref "U11") (pin "59") (pinfunction "PB7_59") (pintype "bidirectional"))
    )
    (net (code "92") (name "PB8.CAN-RX") (class "Default")
      (node (ref "R5") (pin "2") (pinfunction "2_2") (pintype "passive"))
      (node (ref "R6") (pin "2") (pinfunction "2_2") (pintype "passive"))
      (node (ref "U11") (pin "61") (pinfunction "PB8_61") (pintype "bidirectional"))
    )
    (net (code "93") (name "PB9.CAN-TX") (class "Default")
      (node (ref "U11") (pin "62") (pinfunction "PB9_62") (pintype "bidirectional"))
      (node (ref "U6") (pin "1") (pinfunction "TXD_1") (pintype "bidirectional"))
    )
    (net (code "94") (name "PB10.ACC-SCL") (class "Default")
      (node (ref "R46") (pin "1") (pinfunction "1_1") (pintype "passive"))
      (node (ref "U11") (pin "29") (pinfunction "PB10_29") (pintype "bidirectional"))
      (node (ref "U17") (pin "1") (pinfunction "SCL_1") (pintype "input"))
      (node (ref "U5") (pin "14") (pinfunction "SCL/SPC_14") (pintype "input"))
    )
    (net (code "95") (name "PB11.ACC-SDA") (class "Default")
      (node (ref "R30") (pin "2") (pinfunction "2_2") (pintype "passive"))
      (node (ref "U11") (pin "30") (pinfunction "PB11_30") (pintype "bidirectional"))
      (node (ref "U17") (pin "3") (pinfunction "SDA_3") (pintype "bidirectional"))
      (node (ref "U5") (pin "13") (pinfunction "SDA/SDI/SDO_13") (pintype "bidirectional"))
    )
    (net (code "96") (name "PB12.ACC-INT2") (class "Default")
      (node (ref "U11") (pin "33") (pinfunction "PB12_33") (pintype "bidirectional"))
      (node (ref "U5") (pin "9") (pinfunction "INT2_9") (pintype "output"))
    )
    (net (code "97") (name "PB13.ACC-INT1") (class "Default")
      (node (ref "U11") (pin "34") (pinfunction "PB13_34") (pintype "bidirectional"))
      (node (ref "U5") (pin "8") (pinfunction "INT1/RDY_8") (pintype "output"))
    )
    (net (code "98") (name "PB14.LED") (class "Default")
      (node (ref "R40") (pin "2") (pinfunction "2_2") (pintype "passive"))
      (node (ref "U10") (pin "3") (pinfunction "~{CHG}_3") (pintype "output"))
      (node (ref "U11") (pin "35") (pinfunction "PB14_35") (pintype "bidirectional"))
    )
    (net (code "99") (name "PB15.KEY") (class "Default")
      (node (ref "R45") (pin "2") (pinfunction "2_2") (pintype "passive"))
      (node (ref "SW1") (pin "1") (pinfunction "1_1") (pintype "passive"))
      (node (ref "U1") (pin "1") (pinfunction "A_1") (pintype "input"))
      (node (ref "U11") (pin "36") (pinfunction "PB15_36") (pintype "bidirectional"))
    )
    (net (code "100") (name "PC0.SENS-D1") (class "Default")
      (node (ref "C13") (pin "1") (pinfunction "1_1") (pintype "passive"))
      (node (ref "D4") (pin "3") (pinfunction "S_3") (pintype "passive"))
      (node (ref "R27") (pin "2") (pinfunction "2_2") (pintype "passive"))
      (node (ref "U11") (pin "8") (pinfunction "PC0_8") (pintype "bidirectional"))
    )
    (net (code "101") (name "PC2.SENS-A1") (class "Default")
      (node (ref "C40") (pin "1") (pinfunction "1_1") (pintype "passive"))
      (node (ref "D14") (pin "3") (pinfunction "S_3") (pintype "passive"))
      (node (ref "R41") (pin "2") (pinfunction "2_2") (pintype "passive"))
      (node (ref "R42") (pin "2") (pinfunction "2_2") (pintype "passive"))
      (node (ref "U11") (pin "10") (pinfunction "PC2_10") (pintype "bidirectional"))
    )
    (net (code "102") (name "PC4.SD-PWR") (class "Default")
      (node (ref "R7") (pin "1") (pinfunction "1_1") (pintype "passive"))
      (node (ref "U11") (pin "24") (pinfunction "PC4_24") (pintype "bidirectional"))
      (node (ref "U7") (pin "3") (pinfunction "EN_3") (pintype "input"))
    )
    (net (code "103") (name "PC6") (class "Default")
      (node (ref "U11") (pin "37") (pinfunction "PC6_37") (pintype "bidirectional"))
      (node (ref "U3") (pin "CE") (pinfunction "CE_CE") (pintype "input"))
    )
    (net (code "104") (name "PC7") (class "Default")
      (node (ref "U11") (pin "38") (pinfunction "PC7_38") (pintype "bidirectional"))
      (node (ref "U3") (pin "IRQ") (pinfunction "~{IRQ}_IRQ") (pintype "output"))
    )
    (net (code "105") (name "PC9.GSM-DTR") (class "Default")
      (node (ref "GSM-DTR") (pin "TP") (pinfunction "TP_TP") (pintype "input"))
      (node (ref "R14") (pin "1") (pinfunction "1_1") (pintype "passive"))
      (node (ref "U11") (pin "40") (pinfunction "PC9_40") (pintype "bidirectional"))
      (node (ref "U14") (pin "4") (pinfunction "C108/DTR(I)/GPI_E_4") (pintype "input"))
    )
    (net (code "106") (name "PC10.GSM-TXD(I)") (class "Default")
      (node (ref "GSM-TXD") (pin "TP") (pinfunction "TP_TP") (pintype "input"))
      (node (ref "R16") (pin "2") (pinfunction "2_2") (pintype "passive"))
      (node (ref "U11") (pin "51") (pinfunction "PC10_51") (pintype "bidirectional"))
      (node (ref "U14") (pin "7") (pinfunction "C103/TXD(I)_7") (pintype "input"))
    )
    (net (code "107") (name "PC11.GSM-RXD(O)") (class "Default")
      (node (ref "GSM-RXD") (pin "TP") (pinfunction "TP_TP") (pintype "input"))
      (node (ref "U11") (pin "52") (pinfunction "PC11_52") (pintype "bidirectional"))
      (node (ref "U14") (pin "8") (pinfunction "C104/RXD(O)_8") (pintype "output"))
    )
    (net (code "108") (name "PC12.USB_DISC") (class "Default")
      (node (ref "R18") (pin "1") (pinfunction "1_1") (pintype "passive"))
      (node (ref "U11") (pin "53") (pinfunction "PC12_53") (pintype "bidirectional"))
    )
    (net (code "109") (name "PC13.USB_P") (class "Default")
      (node (ref "R20") (pin "2") (pinfunction "2_2") (pintype "passive"))
      (node (ref "R21") (pin "1") (pinfunction "1_1") (pintype "passive"))
      (node (ref "U11") (pin "2") (pinfunction "PC13_2") (pintype "bidirectional"))
    )
    (net (code "110") (name "PD2.CPU_PWR") (class "Default")
      (node (ref "R23") (pin "1") (pinfunction "1_1") (pintype "passive"))
      (node (ref "U1") (pin "2") (pinfunction "B_2") (pintype "input"))
      (node (ref "U11") (pin "54") (pinfunction "PD2_54") (pintype "bidirectional"))
    )
    (net (code "111") (name "PWR-VCC") (class "Default")
      (node (ref "D10") (pin "3") (pinfunction "CC_3") (pintype "passive"))
      (node (ref "LED1") (pin "A") (pinfunction "A_A") (pintype "passive"))
      (node (ref "R22") (pin "1") (pinfunction "1_1") (pintype "passive"))
      (node (ref "R49") (pin "1") (pinfunction "1_1") (pintype "passive"))
      (node (ref "U1") (pin "5") (pinfunction "VCC_5") (pintype "power_in"))
    )
    (net (code "112") (name "RELAY") (class "Default")
      (node (ref "F1") (pin "2") (pinfunction "2_2") (pintype "passive"))
      (node (ref "X1") (pin "8") (pinfunction "8_8") (pintype "passive"))
    )
    (net (code "113") (name "SD-VCC") (class "Default")
      (node (ref "C10") (pin "1") (pinfunction "1_1") (pintype "passive"))
      (node (ref "C41") (pin "2") (pinfunction "2_2") (pintype "passive"))
      (node (ref "C9") (pin "1") (pinfunction "1_1") (pintype "passive"))
      (node (ref "U3") (pin "VDD") (pinfunction "VDD_VDD") (pintype "power_in"))
      (node (ref "U7") (pin "5") (pinfunction "OUT_5") (pintype "passive"))
    )
    (net (code "114") (name "SIMCLK") (class "Default")
      (node (ref "C3") (pin "2") (pinfunction "2_2") (pintype "passive"))
      (node (ref "U14") (pin "11") (pinfunction "SIMCLK_11") (pintype "output"))
      (node (ref "U2") (pin "6") (pinfunction "CLK_6") (pintype "input"))
      (node (ref "U4") (pin "3") (pinfunction "CLK_3") (pintype "input"))
    )
    (net (code "115") (name "SIMIO") (class "Default")
      (node (ref "C2") (pin "1") (pinfunction "1_1") (pintype "passive"))
      (node (ref "JS4") (pin "2") (pinfunction "2_2") (pintype "passive"))
      (node (ref "U14") (pin "12") (pinfunction "SIMIO_12") (pintype "bidirectional"))
      (node (ref "U4") (pin "6") (pinfunction "IO_6") (pintype "bidirectional"))
    )
    (net (code "116") (name "SIMRST") (class "Default")
      (node (ref "C18") (pin "2") (pinfunction "2_2") (pintype "passive"))
      (node (ref "U14") (pin "10") (pinfunction "SIMRST_10") (pintype "output"))
      (node (ref "U2") (pin "7") (pinfunction "RST_7") (pintype "input"))
      (node (ref "U4") (pin "2") (pinfunction "RST_2") (pintype "input"))
    )
    (net (code "117") (name "SIMVCC") (class "Default")
      (node (ref "C4") (pin "2") (pinfunction "2_2") (pintype "passive"))
      (node (ref "U14") (pin "9") (pinfunction "SIMVCC_9") (pintype "passive"))
      (node (ref "U2") (pin "8") (pinfunction "VCC_8") (pintype "passive"))
      (node (ref "U4") (pin "1") (pinfunction "VCC_1") (pintype "passive"))
    )
    (net (code "118") (name "VBAT") (class "Default")
      (node (ref "C37") (pin "2") (pinfunction "2_2") (pintype "passive"))
      (node (ref "D10") (pin "2") (pinfunction "A2_2") (pintype "passive"))
      (node (ref "JP18") (pin "1") (pinfunction "1_1") (pintype "passive"))
      (node (ref "JP3") (pin "2") (pinfunction "2_2") (pintype "passive"))
      (node (ref "Q6") (pin "2") (pinfunction "S_2") (pintype "passive"))
      (node (ref "R36") (pin "2") (pinfunction "2_2") (pintype "passive"))
      (node (ref "R50") (pin "2") (pinfunction "2_2") (pintype "passive"))
      (node (ref "U10") (pin "5") (pinfunction "BAT_5") (pintype "passive"))
    )
    (net (code "119") (name "VDC-4.5V") (class "Default")
      (node (ref "D10") (pin "1") (pinfunction "A1_1") (pintype "passive"))
      (node (ref "D11") (pin "C") (pinfunction "C_C") (pintype "passive"))
      (node (ref "D7") (pin "A") (pinfunction "A_A") (pintype "passive"))
      (node (ref "JP8") (pin "1") (pinfunction "1_1") (pintype "passive"))
      (node (ref "JP9") (pin "2") (pinfunction "2_2") (pintype "passive"))
      (node (ref "R34") (pin "2") (pinfunction "2_2") (pintype "passive"))
    )
    (net (code "120") (name "VDC-5V") (class "Default")
      (node (ref "C14") (pin "2") (pinfunction "2_2") (pintype "passive"))
      (node (ref "C15") (pin "2") (pinfunction "2_2") (pintype "passive"))
      (node (ref "C44") (pin "2") (pinfunction "2_2") (pintype "passive"))
      (node (ref "C52") (pin "2") (pinfunction "2_2") (pintype "passive"))
      (node (ref "C53") (pin "2") (pinfunction "2_2") (pintype "passive"))
      (node (ref "D11") (pin "A") (pinfunction "A_A") (pintype "passive"))
      (node (ref "JP5") (pin "1") (pinfunction "1_1") (pintype "passive"))
      (node (ref "JP9") (pin "1") (pinfunction "1_1") (pintype "passive"))
      (node (ref "L1") (pin "P$2") (pinfunction "2_P$2") (pintype "passive"))
      (node (ref "R47") (pin "2") (pinfunction "2_2") (pintype "passive"))
      (node (ref "R9") (pin "2") (pinfunction "2_2") (pintype "passive"))
      (node (ref "U10") (pin "4") (pinfunction "DC_4") (pintype "input"))
    )
    (net (code "121") (name "VMAIN(4V)") (class "Default")
      (node (ref "C20") (pin "1") (pinfunction "1_1") (pintype "passive"))
      (node (ref "C30") (pin "1") (pinfunction "1_1") (pintype "passive"))
      (node (ref "C31") (pin "2") (pinfunction "2_2") (pintype "passive"))
      (node (ref "C46") (pin "+") (pinfunction "+_+") (pintype "passive"))
      (node (ref "D7") (pin "C") (pinfunction "C_C") (pintype "passive"))
      (node (ref "JP8") (pin "2") (pinfunction "2_2") (pintype "passive"))
      (node (ref "Q1") (pin "2") (pinfunction "S_2") (pintype "passive"))
      (node (ref "Q7") (pin "2") (pinfunction "S_2") (pintype "passive"))
      (node (ref "R1") (pin "2") (pinfunction "2_2") (pintype "passive"))
      (node (ref "U13") (pin "1") (pinfunction "IN_1") (pintype "passive"))
      (node (ref "U13") (pin "3") (pinfunction "EN_3") (pintype "input"))
      (node (ref "U7") (pin "1") (pinfunction "IN_1") (pintype "passive"))
      (node (ref "U9") (pin "1") (pinfunction "IN_1") (pintype "passive"))
    )
    (net (code "122") (name "unconnected-(U2-NC-Pad2)") (class "Default")
      (node (ref "U2") (pin "2") (pinfunction "NC_2") (pintype "no_connect"))
    )
    (net (code "123") (name "unconnected-(U4-NC-Pad5)") (class "Default")
      (node (ref "U4") (pin "5") (pinfunction "NC_5") (pintype "no_connect"))
    )
    (net (code "124") (name "unconnected-(U5-SDO-Pad12)") (class "Default")
      (node (ref "U5") (pin "12") (pinfunction "SDO_12") (pintype "tri_state"))
    )
    (net (code "125") (name "unconnected-(U6-VREF-Pad5)") (class "Default")
      (node (ref "U6") (pin "5") (pinfunction "VREF_5") (pintype "bidirectional"))
    )
    (net (code "126") (name "unconnected-(U7-NC-Pad4)") (class "Default")
      (node (ref "U7") (pin "4") (pinfunction "NC_4") (pintype "no_connect"))
    )
    (net (code "127") (name "unconnected-(U9-NC-Pad4)") (class "Default")
      (node (ref "U9") (pin "4") (pinfunction "NC_4") (pintype "no_connect"))
    )
    (net (code "128") (name "unconnected-(U11F-PC8-Pad39)") (class "Default")
      (node (ref "U11") (pin "39") (pinfunction "PC8_39") (pintype "bidirectional"))
    )
    (net (code "129") (name "unconnected-(U13-NC-Pad4)") (class "Default")
      (node (ref "U13") (pin "4") (pinfunction "NC_4") (pintype "no_connect"))
    )
    (net (code "130") (name "unconnected-(U14-ADC_IN1-Pad13)") (class "Default")
      (node (ref "U14") (pin "13") (pinfunction "ADC_IN1_13") (pintype "input"))
    )
    (net (code "131") (name "unconnected-(U14-ADC_IN2-Pad14)") (class "Default")
      (node (ref "U14") (pin "14") (pinfunction "ADC_IN2_14") (pintype "input"))
    )
    (net (code "132") (name "unconnected-(U14-C107{slash}DSR(O){slash}GPO_C-Pad3)") (class "Default")
      (node (ref "U14") (pin "3") (pinfunction "C107/DSR(O)/GPO_C_3") (pintype "output"))
    )
    (net (code "133") (name "unconnected-(U14-C109{slash}DCD{slash}GPO_A-Pad1)") (class "Default")
      (node (ref "U14") (pin "1") (pinfunction "C109/DCD/GPO_A_1") (pintype "output"))
    )
    (net (code "134") (name "unconnected-(U14-C125{slash}RING{slash}GPO_B-Pad2)") (class "Default")
      (node (ref "U14") (pin "2") (pinfunction "C125/RING/GPO_B_2") (pintype "output"))
    )
    (net (code "135") (name "unconnected-(U14-DAC_OUT-Pad15)") (class "Default")
      (node (ref "U14") (pin "15") (pinfunction "DAC_OUT_15") (pintype "output"))
    )
    (net (code "136") (name "unconnected-(U14-GPIO_01{slash}DVI_WA0-Pad42)") (class "Default")
      (node (ref "U14") (pin "42") (pinfunction "GPIO_01/DVI_WA0_42") (pintype "bidirectional"))
    )
    (net (code "137") (name "unconnected-(U14-GPIO_02{slash}JDR{slash}DVI_RX-Pad41)") (class "Default")
      (node (ref "U14") (pin "41") (pinfunction "GPIO_02/JDR/DVI_RX_41") (pintype "bidirectional"))
    )
    (net (code "138") (name "unconnected-(U14-GPIO_03{slash}DVI_TX-Pad40)") (class "Default")
      (node (ref "U14") (pin "40") (pinfunction "GPIO_03/DVI_TX_40") (pintype "bidirectional"))
    )
    (net (code "139") (name "unconnected-(U14-GPIO_04{slash}DVI_CLK-Pad39)") (class "Default")
      (node (ref "U14") (pin "39") (pinfunction "GPIO_04/DVI_CLK_39") (pintype "bidirectional"))
    )
    (net (code "140") (name "unconnected-(U14-GPIO_05{slash}RFTXMON-Pad29)") (class "Default")
      (node (ref "U14") (pin "29") (pinfunction "GPIO_05/RFTXMON_29") (pintype "bidirectional"))
    )
    (net (code "141") (name "unconnected-(U14-GPIO_06{slash}ALARM-Pad28)") (class "Default")
      (node (ref "U14") (pin "28") (pinfunction "GPIO_06/ALARM_28") (pintype "bidirectional"))
    )
    (net (code "142") (name "unconnected-(U14-GPIO_07{slash}BUZZER-Pad27)") (class "Default")
      (node (ref "U14") (pin "27") (pinfunction "GPIO_07/BUZZER_27") (pintype "bidirectional"))
    )
    (net (code "143") (name "unconnected-(U14-GPIO_08{slash}STAT_LED-Pad26)") (class "Default")
      (node (ref "U14") (pin "26") (pinfunction "GPIO_08/STAT_LED_26") (pintype "bidirectional"))
    )
    (net (code "144") (name "unconnected-(U14-RXD_AUX(I)-Pad44)") (class "Default")
      (node (ref "U14") (pin "44") (pinfunction "RXD_AUX(I)_44") (pintype "input"))
    )
    (net (code "145") (name "unconnected-(U14-TXD_AUX(O)-Pad45)") (class "Default")
      (node (ref "U14") (pin "45") (pinfunction "TXD_AUX(O)_45") (pintype "output"))
    )
    (net (code "146") (name "unconnected-(U14-VRTC-Pad30)") (class "Default")
      (node (ref "U14") (pin "30") (pinfunction "VRTC_30") (pintype "passive"))
    )
    (net (code "147") (name "unconnected-(U15-1PPS-Pad3)") (class "Default")
      (node (ref "U15") (pin "3") (pinfunction "1PPS_3") (pintype "output"))
    )
    (net (code "148") (name "unconnected-(U15-CAN0RX-Pad2)") (class "Default")
      (node (ref "U15") (pin "2") (pinfunction "CAN0RX_2") (pintype "input"))
    )
    (net (code "149") (name "unconnected-(U15-CAN0TX-Pad1)") (class "Default")
      (node (ref "U15") (pin "1") (pinfunction "CAN0TX_1") (pintype "output"))
    )
    (net (code "150") (name "unconnected-(U15-EXT_INT-Pad4)") (class "Default")
      (node (ref "U15") (pin "4") (pinfunction "EXT_INT_4") (pintype "bidirectional"))
    )
    (net (code "151") (name "unconnected-(U15-NC-Pad8)") (class "Default")
      (node (ref "U15") (pin "8") (pinfunction "NC_8") (pintype "no_connect"))
    )
    (net (code "152") (name "unconnected-(U15-NC-Pad16)") (class "Default")
      (node (ref "U15") (pin "16") (pinfunction "NC_16") (pintype "no_connect"))
    )
    (net (code "153") (name "unconnected-(U15-NC-Pad17)") (class "Default")
      (node (ref "U15") (pin "17") (pinfunction "NC_17") (pintype "no_connect"))
    )
    (net (code "154") (name "unconnected-(U15-SCL2-Pad19)") (class "Default")
      (node (ref "U15") (pin "19") (pinfunction "SCL2_19") (pintype "bidirectional"))
    )
    (net (code "155") (name "unconnected-(U15-SDA2-Pad18)") (class "Default")
      (node (ref "U15") (pin "18") (pinfunction "SDA2_18") (pintype "bidirectional"))
    )
    (net (code "156") (name "unconnected-(U15-USB_DM-Pad5)") (class "Default")
      (node (ref "U15") (pin "5") (pinfunction "USB_DM_5") (pintype "bidirectional"))
    )
    (net (code "157") (name "unconnected-(U15-USB_DP-Pad6)") (class "Default")
      (node (ref "U15") (pin "6") (pinfunction "USB_DP_6") (pintype "bidirectional"))
    )
    (net (code "158") (name "unconnected-(X1-Pad7)") (class "Default")
      (node (ref "X1") (pin "7") (pinfunction "7_7") (pintype "passive"))
    )
    (net (code "159") (name "unconnected-(X2-PadID)") (class "Default")
      (node (ref "X2") (pin "ID") (pinfunction "ID_ID") (pintype "bidirectional"))
    )
  )
)
